# Power_Supply.net
KiCad netlist of a schematic drawn in Altium Designer
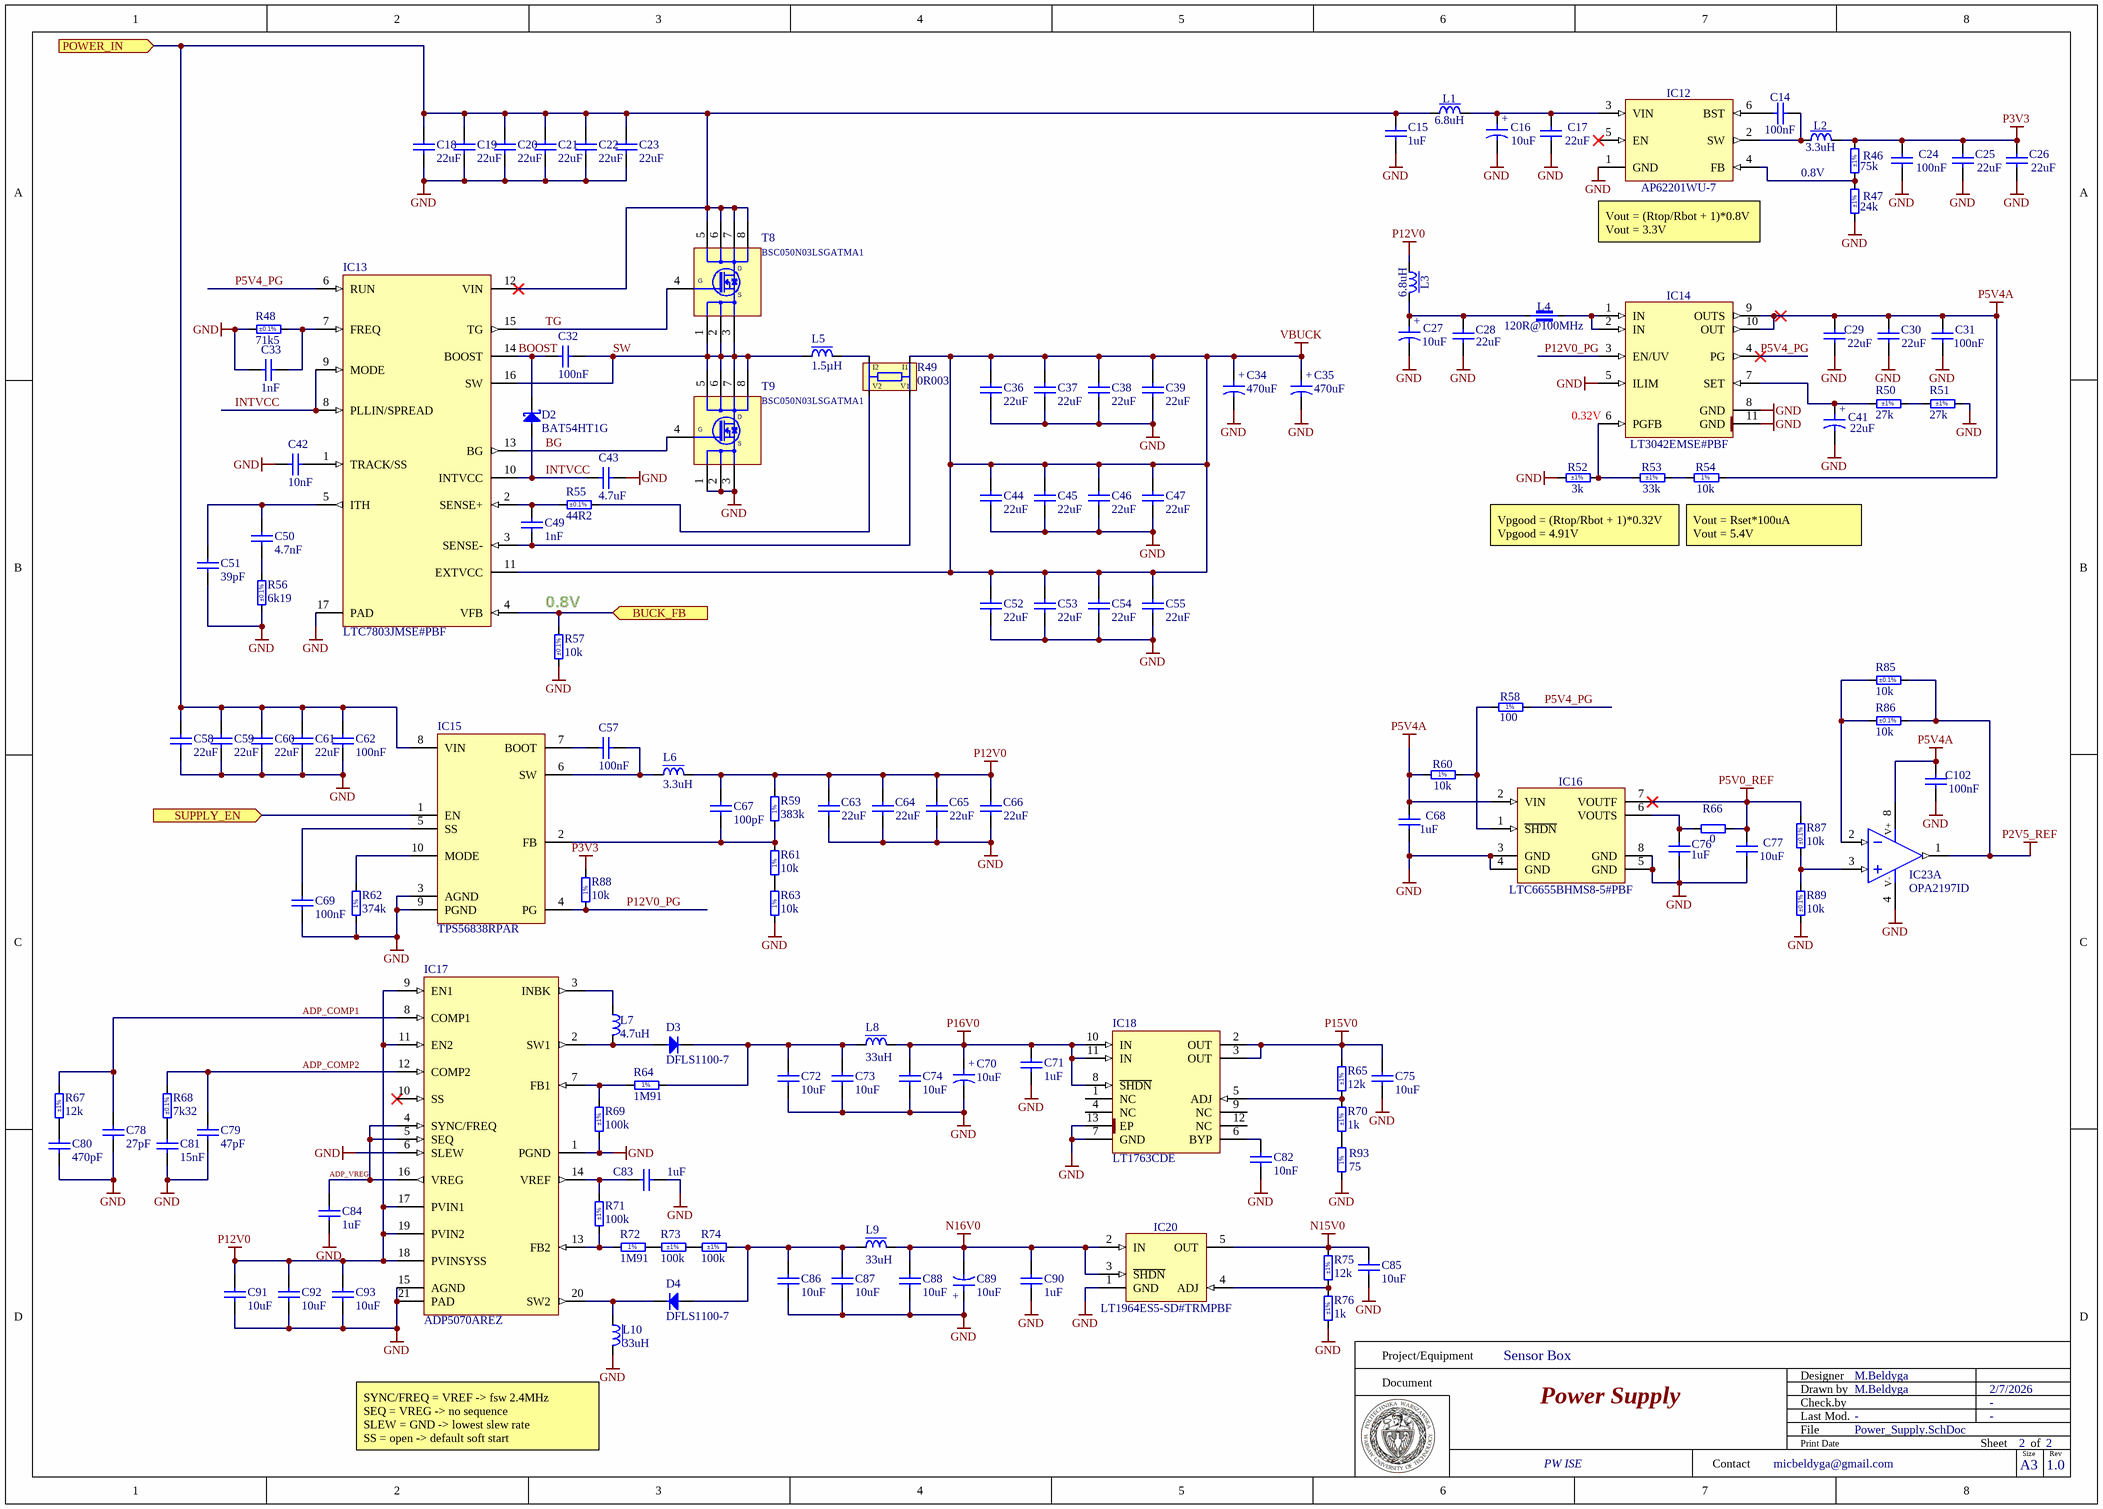
[diagram p0: Power_Supply.SchDoc]

(export (version "E")
  (design (tool "Eeschema 10.0.6"))
  (components
    (comp (ref "C14")
      (value "100nF")
      (footprint "CAPC1005X55N")
      (description "Non-polarised capacitor")
      (fields
        (field (name "PART NUMBER") "CC0402_100NF_16V_10%_X5R")
        (field (name "VOLTAGE") "16V")
        (field (name "AUTHOR") "CERN DEM JLC")
      )
      (libsource (lib "Capacitors") (part "Capacitor - non polarized"))
    )
    (comp (ref "C15")
      (value "1uF")
      (footprint "CAPC1608X87N")
      (description "Non-polarised capacitor")
      (fields
        (field (name "PART NUMBER") "CC0603_1UF_25V_10%_X7R")
        (field (name "VOLTAGE") "25V")
        (field (name "AUTHOR") "CERN DEM JLC")
      )
      (libsource (lib "Capacitors") (part "Capacitor - non polarized"))
    )
    (comp (ref "C16")
      (value "10uF")
      (footprint "CAPMP3216X180N")
      (description "Polarised capacitor")
      (fields
        (field (name "PART NUMBER") "CTE3216-18_10UF_16V_20%_AVX_TCJ")
        (field (name "VOLTAGE") "16V")
        (field (name "AUTHOR") "CERN DEM JLC")
      )
      (libsource (lib "Capacitors") (part "Capacitor - polarized"))
    )
    (comp (ref "C17")
      (value "22uF")
      (footprint "CAPC2012X135N")
      (description "Non-polarised capacitor")
      (fields
        (field (name "PART NUMBER") "CC0805_22UF_16V_10%_X5R")
        (field (name "VOLTAGE") "16V")
        (field (name "AUTHOR") "CERN DEM JLC")
      )
      (libsource (lib "Capacitors") (part "Capacitor - non polarized"))
    )
    (comp (ref "C18")
      (value "22uF")
      (footprint "CAPC3216X180N")
      (description "Non-polarised capacitor")
      (fields
        (field (name "PART NUMBER") "CC1206_22UF_35V_20%_X5R")
        (field (name "VOLTAGE") "35V")
        (field (name "AUTHOR") "CERN DEM BC")
      )
      (libsource (lib "Capacitors") (part "Capacitor - non polarized"))
    )
    (comp (ref "C19")
      (value "22uF")
      (footprint "CAPC3216X180N")
      (description "Non-polarised capacitor")
      (fields
        (field (name "PART NUMBER") "CC1206_22UF_35V_20%_X5R")
        (field (name "VOLTAGE") "35V")
        (field (name "AUTHOR") "CERN DEM BC")
      )
      (libsource (lib "Capacitors") (part "Capacitor - non polarized"))
    )
    (comp (ref "C20")
      (value "22uF")
      (footprint "CAPC3216X180N")
      (description "Non-polarised capacitor")
      (fields
        (field (name "PART NUMBER") "CC1206_22UF_35V_20%_X5R")
        (field (name "VOLTAGE") "35V")
        (field (name "AUTHOR") "CERN DEM BC")
      )
      (libsource (lib "Capacitors") (part "Capacitor - non polarized"))
    )
    (comp (ref "C21")
      (value "22uF")
      (footprint "CAPC3216X180N")
      (description "Non-polarised capacitor")
      (fields
        (field (name "PART NUMBER") "CC1206_22UF_35V_20%_X5R")
        (field (name "VOLTAGE") "35V")
        (field (name "AUTHOR") "CERN DEM BC")
      )
      (libsource (lib "Capacitors") (part "Capacitor - non polarized"))
    )
    (comp (ref "C22")
      (value "22uF")
      (footprint "CAPC3216X180N")
      (description "Non-polarised capacitor")
      (fields
        (field (name "PART NUMBER") "CC1206_22UF_35V_20%_X5R")
        (field (name "VOLTAGE") "35V")
        (field (name "AUTHOR") "CERN DEM BC")
      )
      (libsource (lib "Capacitors") (part "Capacitor - non polarized"))
    )
    (comp (ref "C23")
      (value "22uF")
      (footprint "CAPC3216X180N")
      (description "Non-polarised capacitor")
      (fields
        (field (name "PART NUMBER") "CC1206_22UF_35V_20%_X5R")
        (field (name "VOLTAGE") "35V")
        (field (name "AUTHOR") "CERN DEM BC")
      )
      (libsource (lib "Capacitors") (part "Capacitor - non polarized"))
    )
    (comp (ref "C24")
      (value "100nF")
      (footprint "CAPC1005X55N")
      (description "Non-polarised capacitor")
      (fields
        (field (name "PART NUMBER") "CC0402_100NF_16V_10%_X5R")
        (field (name "VOLTAGE") "16V")
        (field (name "AUTHOR") "CERN DEM JLC")
      )
      (libsource (lib "Capacitors") (part "Capacitor - non polarized"))
    )
    (comp (ref "C25")
      (value "22uF")
      (footprint "CAPC2012X135N")
      (description "Non-polarised capacitor")
      (fields
        (field (name "PART NUMBER") "CC0805_22UF_16V_10%_X5R")
        (field (name "VOLTAGE") "16V")
        (field (name "AUTHOR") "CERN DEM JLC")
      )
      (libsource (lib "Capacitors") (part "Capacitor - non polarized"))
    )
    (comp (ref "C26")
      (value "22uF")
      (footprint "CAPC2012X135N")
      (description "Non-polarised capacitor")
      (fields
        (field (name "PART NUMBER") "CC0805_22UF_16V_10%_X5R")
        (field (name "VOLTAGE") "16V")
        (field (name "AUTHOR") "CERN DEM JLC")
      )
      (libsource (lib "Capacitors") (part "Capacitor - non polarized"))
    )
    (comp (ref "C27")
      (value "10uF")
      (footprint "CAPMP3216X180N")
      (description "Polarised capacitor")
      (fields
        (field (name "PART NUMBER") "CTE3216-18_10UF_16V_20%_AVX_TCJ")
        (field (name "VOLTAGE") "16V")
        (field (name "AUTHOR") "CERN DEM JLC")
      )
      (libsource (lib "Capacitors") (part "Capacitor - polarized"))
    )
    (comp (ref "C28")
      (value "22uF")
      (footprint "CAPC2012X135N")
      (description "Non-polarised capacitor")
      (fields
        (field (name "PART NUMBER") "CC0805_22UF_16V_10%_X5R")
        (field (name "VOLTAGE") "16V")
        (field (name "AUTHOR") "CERN DEM JLC")
      )
      (libsource (lib "Capacitors") (part "Capacitor - non polarized"))
    )
    (comp (ref "C29")
      (value "22uF")
      (footprint "CAPC2012X135N")
      (description "Non-polarised capacitor")
      (fields
        (field (name "PART NUMBER") "CC0805_22UF_16V_10%_X5R")
        (field (name "VOLTAGE") "16V")
        (field (name "AUTHOR") "CERN DEM JLC")
      )
      (libsource (lib "Capacitors") (part "Capacitor - non polarized"))
    )
    (comp (ref "C30")
      (value "22uF")
      (footprint "CAPC2012X135N")
      (description "Non-polarised capacitor")
      (fields
        (field (name "PART NUMBER") "CC0805_22UF_16V_10%_X5R")
        (field (name "VOLTAGE") "16V")
        (field (name "AUTHOR") "CERN DEM JLC")
      )
      (libsource (lib "Capacitors") (part "Capacitor - non polarized"))
    )
    (comp (ref "C31")
      (value "100nF")
      (footprint "CAPC1005X55N")
      (description "Non-polarised capacitor")
      (fields
        (field (name "PART NUMBER") "CC0402_100NF_16V_10%_X5R")
        (field (name "VOLTAGE") "16V")
        (field (name "AUTHOR") "CERN DEM JLC")
      )
      (libsource (lib "Capacitors") (part "Capacitor - non polarized"))
    )
    (comp (ref "C32")
      (value "100nF")
      (footprint "CAPC1005X55N")
      (description "Non-polarised capacitor")
      (fields
        (field (name "PART NUMBER") "CC0402_100NF_50V_10%_X7R")
        (field (name "VOLTAGE") "50V")
        (field (name "AUTHOR") "CERN DEM MR")
      )
      (libsource (lib "Capacitors") (part "Capacitor - non polarized"))
    )
    (comp (ref "C33")
      (value "1nF")
      (footprint "CAPC1005X55N")
      (description "Non-polarised capacitor")
      (fields
        (field (name "PART NUMBER") "CC0402_1NF_50V_5%_C0G")
        (field (name "VOLTAGE") "50V")
        (field (name "AUTHOR") "CERN DEM BC")
      )
      (libsource (lib "Capacitors") (part "Capacitor - non polarized"))
    )
    (comp (ref "C34")
      (value "470uF")
      (footprint "CAPAE1030X1020N")
      (description "Polarised capacitor")
      (fields
        (field (name "PART NUMBER") "CAE1030-1020_470UF_25V_20%")
        (field (name "VOLTAGE") "25V")
        (field (name "AUTHOR") "CERN DEM JLC")
      )
      (libsource (lib "Capacitors") (part "Capacitor - polarized"))
    )
    (comp (ref "C35")
      (value "470uF")
      (footprint "CAPAE1030X1020N")
      (description "Polarised capacitor")
      (fields
        (field (name "PART NUMBER") "CAE1030-1020_470UF_25V_20%")
        (field (name "VOLTAGE") "25V")
        (field (name "AUTHOR") "CERN DEM JLC")
      )
      (libsource (lib "Capacitors") (part "Capacitor - polarized"))
    )
    (comp (ref "C36")
      (value "22uF")
      (footprint "CAPC3216X180N")
      (description "Non-polarised capacitor")
      (fields
        (field (name "PART NUMBER") "CC1206_22UF_25V_20%_X5R")
        (field (name "VOLTAGE") "25V")
        (field (name "AUTHOR") "CERN DEM WB")
      )
      (libsource (lib "Capacitors") (part "Capacitor - non polarized"))
    )
    (comp (ref "C37")
      (value "22uF")
      (footprint "CAPC3216X180N")
      (description "Non-polarised capacitor")
      (fields
        (field (name "PART NUMBER") "CC1206_22UF_25V_20%_X5R")
        (field (name "VOLTAGE") "25V")
        (field (name "AUTHOR") "CERN DEM WB")
      )
      (libsource (lib "Capacitors") (part "Capacitor - non polarized"))
    )
    (comp (ref "C38")
      (value "22uF")
      (footprint "CAPC3216X180N")
      (description "Non-polarised capacitor")
      (fields
        (field (name "PART NUMBER") "CC1206_22UF_25V_20%_X5R")
        (field (name "VOLTAGE") "25V")
        (field (name "AUTHOR") "CERN DEM WB")
      )
      (libsource (lib "Capacitors") (part "Capacitor - non polarized"))
    )
    (comp (ref "C39")
      (value "22uF")
      (footprint "CAPC3216X180N")
      (description "Non-polarised capacitor")
      (fields
        (field (name "PART NUMBER") "CC1206_22UF_25V_20%_X5R")
        (field (name "VOLTAGE") "25V")
        (field (name "AUTHOR") "CERN DEM WB")
      )
      (libsource (lib "Capacitors") (part "Capacitor - non polarized"))
    )
    (comp (ref "C41")
      (value "22uF")
      (footprint "CAPMP3528X210N")
      (description "Polarised capacitor")
      (fields
        (field (name "PART NUMBER") "CTE3528-21_22UF_10V_10%_LESR0700")
        (field (name "VOLTAGE") "10V")
        (field (name "AUTHOR") "CERN DEM JLC")
      )
      (libsource (lib "Capacitors") (part "Capacitor - polarized"))
    )
    (comp (ref "C42")
      (value "10nF")
      (footprint "CAPC1005X55N")
      (description "Non-polarised capacitor")
      (fields
        (field (name "PART NUMBER") "CC0402_10NF_25V_10%_X7R")
        (field (name "VOLTAGE") "25V")
        (field (name "AUTHOR") "CERN DEM JLC")
      )
      (libsource (lib "Capacitors") (part "Capacitor - non polarized"))
    )
    (comp (ref "C43")
      (value "4.7uF")
      (footprint "CAPC1005X55N")
      (description "Non-polarised capacitor")
      (fields
        (field (name "PART NUMBER") "CC0402_4.7UF_10V_10%_X5R")
        (field (name "VOLTAGE") "10V")
        (field (name "AUTHOR") "CERN DEM BC")
      )
      (libsource (lib "Capacitors") (part "Capacitor - non polarized"))
    )
    (comp (ref "C44")
      (value "22uF")
      (footprint "CAPC3216X180N")
      (description "Non-polarised capacitor")
      (fields
        (field (name "PART NUMBER") "CC1206_22UF_25V_20%_X5R")
        (field (name "VOLTAGE") "25V")
        (field (name "AUTHOR") "CERN DEM WB")
      )
      (libsource (lib "Capacitors") (part "Capacitor - non polarized"))
    )
    (comp (ref "C45")
      (value "22uF")
      (footprint "CAPC3216X180N")
      (description "Non-polarised capacitor")
      (fields
        (field (name "PART NUMBER") "CC1206_22UF_25V_20%_X5R")
        (field (name "VOLTAGE") "25V")
        (field (name "AUTHOR") "CERN DEM WB")
      )
      (libsource (lib "Capacitors") (part "Capacitor - non polarized"))
    )
    (comp (ref "C46")
      (value "22uF")
      (footprint "CAPC3216X180N")
      (description "Non-polarised capacitor")
      (fields
        (field (name "PART NUMBER") "CC1206_22UF_25V_20%_X5R")
        (field (name "VOLTAGE") "25V")
        (field (name "AUTHOR") "CERN DEM WB")
      )
      (libsource (lib "Capacitors") (part "Capacitor - non polarized"))
    )
    (comp (ref "C47")
      (value "22uF")
      (footprint "CAPC3216X180N")
      (description "Non-polarised capacitor")
      (fields
        (field (name "PART NUMBER") "CC1206_22UF_25V_20%_X5R")
        (field (name "VOLTAGE") "25V")
        (field (name "AUTHOR") "CERN DEM WB")
      )
      (libsource (lib "Capacitors") (part "Capacitor - non polarized"))
    )
    (comp (ref "C49")
      (value "1nF")
      (footprint "CAPC1005X55N")
      (description "Non-polarised capacitor")
      (fields
        (field (name "PART NUMBER") "CC0402_1NF_50V_5%_C0G")
        (field (name "VOLTAGE") "50V")
        (field (name "AUTHOR") "CERN DEM BC")
      )
      (libsource (lib "Capacitors") (part "Capacitor - non polarized"))
    )
    (comp (ref "C50")
      (value "4.7nF")
      (footprint "CAPC1005X55N")
      (description "Non-polarised capacitor")
      (fields
        (field (name "PART NUMBER") "CC0402_4.7NF_16V_10%_X7R")
        (field (name "VOLTAGE") "16V")
        (field (name "AUTHOR") "CERN DEM JLC")
      )
      (libsource (lib "Capacitors") (part "Capacitor - non polarized"))
    )
    (comp (ref "C51")
      (value "39pF")
      (footprint "CAPC1005X55N")
      (description "Non-polarised capacitor")
      (fields
        (field (name "PART NUMBER") "CC0402_39PF_100V_5%_C0G_MURATA_GRM1555C2A390JA01")
        (field (name "VOLTAGE") "100V")
        (field (name "AUTHOR") "CERN DEM BC")
      )
      (libsource (lib "Capacitors") (part "Capacitor - non polarized"))
    )
    (comp (ref "C52")
      (value "22uF")
      (footprint "CAPC3216X180N")
      (description "Non-polarised capacitor")
      (fields
        (field (name "PART NUMBER") "CC1206_22UF_25V_20%_X5R")
        (field (name "VOLTAGE") "25V")
        (field (name "AUTHOR") "CERN DEM WB")
      )
      (libsource (lib "Capacitors") (part "Capacitor - non polarized"))
    )
    (comp (ref "C53")
      (value "22uF")
      (footprint "CAPC3216X180N")
      (description "Non-polarised capacitor")
      (fields
        (field (name "PART NUMBER") "CC1206_22UF_25V_20%_X5R")
        (field (name "VOLTAGE") "25V")
        (field (name "AUTHOR") "CERN DEM WB")
      )
      (libsource (lib "Capacitors") (part "Capacitor - non polarized"))
    )
    (comp (ref "C54")
      (value "22uF")
      (footprint "CAPC3216X180N")
      (description "Non-polarised capacitor")
      (fields
        (field (name "PART NUMBER") "CC1206_22UF_25V_20%_X5R")
        (field (name "VOLTAGE") "25V")
        (field (name "AUTHOR") "CERN DEM WB")
      )
      (libsource (lib "Capacitors") (part "Capacitor - non polarized"))
    )
    (comp (ref "C55")
      (value "22uF")
      (footprint "CAPC3216X180N")
      (description "Non-polarised capacitor")
      (fields
        (field (name "PART NUMBER") "CC1206_22UF_25V_20%_X5R")
        (field (name "VOLTAGE") "25V")
        (field (name "AUTHOR") "CERN DEM WB")
      )
      (libsource (lib "Capacitors") (part "Capacitor - non polarized"))
    )
    (comp (ref "C57")
      (value "100nF")
      (footprint "CAPC1005X55N")
      (description "Non-polarised capacitor")
      (fields
        (field (name "PART NUMBER") "CC0402_100NF_16V_10%_X5R")
        (field (name "VOLTAGE") "16V")
        (field (name "AUTHOR") "CERN DEM JLC")
      )
      (libsource (lib "Capacitors") (part "Capacitor - non polarized"))
    )
    (comp (ref "C58")
      (value "22uF")
      (footprint "CAPC3216X180N")
      (description "Non-polarised capacitor")
      (fields
        (field (name "PART NUMBER") "CC1206_22UF_35V_20%_X5R")
        (field (name "VOLTAGE") "35V")
        (field (name "AUTHOR") "CERN DEM BC")
      )
      (libsource (lib "Capacitors") (part "Capacitor - non polarized"))
    )
    (comp (ref "C59")
      (value "22uF")
      (footprint "CAPC3216X180N")
      (description "Non-polarised capacitor")
      (fields
        (field (name "PART NUMBER") "CC1206_22UF_35V_20%_X5R")
        (field (name "VOLTAGE") "35V")
        (field (name "AUTHOR") "CERN DEM BC")
      )
      (libsource (lib "Capacitors") (part "Capacitor - non polarized"))
    )
    (comp (ref "C60")
      (value "22uF")
      (footprint "CAPC3216X180N")
      (description "Non-polarised capacitor")
      (fields
        (field (name "PART NUMBER") "CC1206_22UF_35V_20%_X5R")
        (field (name "VOLTAGE") "35V")
        (field (name "AUTHOR") "CERN DEM BC")
      )
      (libsource (lib "Capacitors") (part "Capacitor - non polarized"))
    )
    (comp (ref "C61")
      (value "22uF")
      (footprint "CAPC3216X180N")
      (description "Non-polarised capacitor")
      (fields
        (field (name "PART NUMBER") "CC1206_22UF_35V_20%_X5R")
        (field (name "VOLTAGE") "35V")
        (field (name "AUTHOR") "CERN DEM BC")
      )
      (libsource (lib "Capacitors") (part "Capacitor - non polarized"))
    )
    (comp (ref "C62")
      (value "100nF")
      (footprint "CAPC1005X55N")
      (description "Non-polarised capacitor")
      (fields
        (field (name "PART NUMBER") "CC0402_100NF_16V_10%_X5R")
        (field (name "VOLTAGE") "16V")
        (field (name "AUTHOR") "CERN DEM JLC")
      )
      (libsource (lib "Capacitors") (part "Capacitor - non polarized"))
    )
    (comp (ref "C63")
      (value "22uF")
      (footprint "CAPC2012X135N")
      (description "Non-polarised capacitor")
      (fields
        (field (name "PART NUMBER") "CC0805_22UF_16V_10%_X5R")
        (field (name "VOLTAGE") "16V")
        (field (name "AUTHOR") "CERN DEM JLC")
      )
      (libsource (lib "Capacitors") (part "Capacitor - non polarized"))
    )
    (comp (ref "C64")
      (value "22uF")
      (footprint "CAPC2012X135N")
      (description "Non-polarised capacitor")
      (fields
        (field (name "PART NUMBER") "CC0805_22UF_16V_10%_X5R")
        (field (name "VOLTAGE") "16V")
        (field (name "AUTHOR") "CERN DEM JLC")
      )
      (libsource (lib "Capacitors") (part "Capacitor - non polarized"))
    )
    (comp (ref "C65")
      (value "22uF")
      (footprint "CAPC2012X135N")
      (description "Non-polarised capacitor")
      (fields
        (field (name "PART NUMBER") "CC0805_22UF_16V_10%_X5R")
        (field (name "VOLTAGE") "16V")
        (field (name "AUTHOR") "CERN DEM JLC")
      )
      (libsource (lib "Capacitors") (part "Capacitor - non polarized"))
    )
    (comp (ref "C66")
      (value "22uF")
      (footprint "CAPC2012X135N")
      (description "Non-polarised capacitor")
      (fields
        (field (name "PART NUMBER") "CC0805_22UF_16V_10%_X5R")
        (field (name "VOLTAGE") "16V")
        (field (name "AUTHOR") "CERN DEM JLC")
      )
      (libsource (lib "Capacitors") (part "Capacitor - non polarized"))
    )
    (comp (ref "C67")
      (value "100pF")
      (footprint "CAPC1005X55N")
      (description "SMD Mulitlayer Ceramic Chip Capacitor")
      (fields
        (field (name "PART NUMBER") "CC0402_100PF_50V_5%_C0G")
        (field (name "VOLTAGE") "50V")
        (field (name "AUTHOR") "Michal Beldyga")
      )
      (libsource (lib "Capacitors") (part "Capacitor - non polarized"))
    )
    (comp (ref "C68")
      (value "1uF")
      (footprint "CAPC1608X87N")
      (description "Non-polarised capacitor")
      (fields
        (field (name "PART NUMBER") "CC0603_1UF_25V_10%_X7R")
        (field (name "VOLTAGE") "25V")
        (field (name "AUTHOR") "CERN DEM JLC")
      )
      (libsource (lib "Capacitors") (part "Capacitor - non polarized"))
    )
    (comp (ref "C69")
      (value "100nF")
      (footprint "CAPC1005X55N")
      (description "Non-polarised capacitor")
      (fields
        (field (name "PART NUMBER") "CC0402_100NF_16V_10%_X5R")
        (field (name "VOLTAGE") "16V")
        (field (name "AUTHOR") "CERN DEM JLC")
      )
      (libsource (lib "Capacitors") (part "Capacitor - non polarized"))
    )
    (comp (ref "C70")
      (value "10uF")
      (footprint "CAPMP3216X180N")
      (description "Polarised capacitor")
      (fields
        (field (name "PART NUMBER") "CTE3216-18_10UF_16V_20%_AVX_TCJ")
        (field (name "VOLTAGE") "16V")
        (field (name "AUTHOR") "CERN DEM JLC")
      )
      (libsource (lib "Capacitors") (part "Capacitor - polarized"))
    )
    (comp (ref "C71")
      (value "1uF")
      (footprint "CAPC1608X87N")
      (description "Non-polarised capacitor")
      (fields
        (field (name "PART NUMBER") "CC0603_1UF_25V_10%_X7R")
        (field (name "VOLTAGE") "25V")
        (field (name "AUTHOR") "CERN DEM JLC")
      )
      (libsource (lib "Capacitors") (part "Capacitor - non polarized"))
    )
    (comp (ref "C72")
      (value "10uF")
      (footprint "CAPC1709X100N")
      (description "Non-polarised capacitor")
      (fields
        (field (name "PART NUMBER") "CC0603_10UF_25V_20%_X5R")
        (field (name "VOLTAGE") "25V")
        (field (name "AUTHOR") "CERN DEM BC")
      )
      (libsource (lib "Capacitors") (part "Capacitor - non polarized"))
    )
    (comp (ref "C73")
      (value "10uF")
      (footprint "CAPC1709X100N")
      (description "Non-polarised capacitor")
      (fields
        (field (name "PART NUMBER") "CC0603_10UF_25V_20%_X5R")
        (field (name "VOLTAGE") "25V")
        (field (name "AUTHOR") "CERN DEM BC")
      )
      (libsource (lib "Capacitors") (part "Capacitor - non polarized"))
    )
    (comp (ref "C74")
      (value "10uF")
      (footprint "CAPC1709X100N")
      (description "Non-polarised capacitor")
      (fields
        (field (name "PART NUMBER") "CC0603_10UF_25V_20%_X5R")
        (field (name "VOLTAGE") "25V")
        (field (name "AUTHOR") "CERN DEM BC")
      )
      (libsource (lib "Capacitors") (part "Capacitor - non polarized"))
    )
    (comp (ref "C75")
      (value "10uF")
      (footprint "CAPC1709X100N")
      (description "Non-polarised capacitor")
      (fields
        (field (name "PART NUMBER") "CC0603_10UF_25V_20%_X5R")
        (field (name "VOLTAGE") "25V")
        (field (name "AUTHOR") "CERN DEM BC")
      )
      (libsource (lib "Capacitors") (part "Capacitor - non polarized"))
    )
    (comp (ref "C76")
      (value "1uF")
      (footprint "CAPC1608X87N")
      (description "Non-polarised capacitor")
      (fields
        (field (name "PART NUMBER") "CC0603_1UF_25V_10%_X7R")
        (field (name "VOLTAGE") "25V")
        (field (name "AUTHOR") "CERN DEM JLC")
      )
      (libsource (lib "Capacitors") (part "Capacitor - non polarized"))
    )
    (comp (ref "C77")
      (value "10uF")
      (footprint "CAPC1608X80N")
      (description "Non-polarised capacitor")
      (fields
        (field (name "PART NUMBER") "CC0603_10UF_16V_20%_X5R")
        (field (name "VOLTAGE") "16V")
        (field (name "AUTHOR") "CERN DEM MR")
      )
      (libsource (lib "Capacitors") (part "Capacitor - non polarized"))
    )
    (comp (ref "C78")
      (value "27pF")
      (footprint "CAPC1005X55N")
      (description "Non-polarised capacitor")
      (fields
        (field (name "PART NUMBER") "CC0402_27PF_50V_5%_C0G")
        (field (name "VOLTAGE") "50V")
        (field (name "AUTHOR") "CERN DEM JLC")
      )
      (libsource (lib "Capacitors") (part "Capacitor - non polarized"))
    )
    (comp (ref "C79")
      (value "47pF")
      (footprint "CAPC1005X55N")
      (description "Non-polarised capacitor")
      (fields
        (field (name "PART NUMBER") "CC0402_47PF_50V_5%_C0G")
        (field (name "VOLTAGE") "50V")
        (field (name "AUTHOR") "CERN DEM JLC")
      )
      (libsource (lib "Capacitors") (part "Capacitor - non polarized"))
    )
    (comp (ref "C80")
      (value "470pF")
      (footprint "CAPC1005X55N")
      (description "Non-polarised capacitor")
      (fields
        (field (name "PART NUMBER") "CC0402_470PF_50V_10%_X7R")
        (field (name "VOLTAGE") "50V")
        (field (name "AUTHOR") "CERN DEM JLC")
      )
      (libsource (lib "Capacitors") (part "Capacitor - non polarized"))
    )
    (comp (ref "C81")
      (value "15nF")
      (footprint "CAPC1005X55N")
      (description "Non-polarised capacitor")
      (fields
        (field (name "PART NUMBER") "CC0402_15NF_50V_5%_X7R")
        (field (name "VOLTAGE") "50V")
        (field (name "AUTHOR") "CERN DEM BC")
      )
      (libsource (lib "Capacitors") (part "Capacitor - non polarized"))
    )
    (comp (ref "C82")
      (value "10nF")
      (footprint "CAPC1005X55N")
      (description "Non-polarised capacitor")
      (fields
        (field (name "PART NUMBER") "CC0402_10NF_50V_5%_X7R")
        (field (name "VOLTAGE") "50V")
        (field (name "AUTHOR") "CERN DEM BC")
      )
      (libsource (lib "Capacitors") (part "Capacitor - non polarized"))
    )
    (comp (ref "C83")
      (value "1uF")
      (footprint "CAPC1608X87N")
      (description "Non-polarised capacitor")
      (fields
        (field (name "PART NUMBER") "CC0603_1UF_25V_10%_X7R")
        (field (name "VOLTAGE") "25V")
        (field (name "AUTHOR") "CERN DEM JLC")
      )
      (libsource (lib "Capacitors") (part "Capacitor - non polarized"))
    )
    (comp (ref "C84")
      (value "1uF")
      (footprint "CAPC1608X87N")
      (description "Non-polarised capacitor")
      (fields
        (field (name "PART NUMBER") "CC0603_1UF_25V_10%_X7R")
        (field (name "VOLTAGE") "25V")
        (field (name "AUTHOR") "CERN DEM JLC")
      )
      (libsource (lib "Capacitors") (part "Capacitor - non polarized"))
    )
    (comp (ref "C85")
      (value "10uF")
      (footprint "CAPC1709X100N")
      (description "Non-polarised capacitor")
      (fields
        (field (name "PART NUMBER") "CC0603_10UF_25V_20%_X5R")
        (field (name "VOLTAGE") "25V")
        (field (name "AUTHOR") "CERN DEM BC")
      )
      (libsource (lib "Capacitors") (part "Capacitor - non polarized"))
    )
    (comp (ref "C86")
      (value "10uF")
      (footprint "CAPC1709X100N")
      (description "Non-polarised capacitor")
      (fields
        (field (name "PART NUMBER") "CC0603_10UF_25V_20%_X5R")
        (field (name "VOLTAGE") "25V")
        (field (name "AUTHOR") "CERN DEM BC")
      )
      (libsource (lib "Capacitors") (part "Capacitor - non polarized"))
    )
    (comp (ref "C87")
      (value "10uF")
      (footprint "CAPC1709X100N")
      (description "Non-polarised capacitor")
      (fields
        (field (name "PART NUMBER") "CC0603_10UF_25V_20%_X5R")
        (field (name "VOLTAGE") "25V")
        (field (name "AUTHOR") "CERN DEM BC")
      )
      (libsource (lib "Capacitors") (part "Capacitor - non polarized"))
    )
    (comp (ref "C88")
      (value "10uF")
      (footprint "CAPC1709X100N")
      (description "Non-polarised capacitor")
      (fields
        (field (name "PART NUMBER") "CC0603_10UF_25V_20%_X5R")
        (field (name "VOLTAGE") "25V")
        (field (name "AUTHOR") "CERN DEM BC")
      )
      (libsource (lib "Capacitors") (part "Capacitor - non polarized"))
    )
    (comp (ref "C89")
      (value "10uF")
      (footprint "CAPMP3216X180N")
      (description "Polarised capacitor")
      (fields
        (field (name "PART NUMBER") "CTE3216-18_10UF_16V_20%_AVX_TCJ")
        (field (name "VOLTAGE") "16V")
        (field (name "AUTHOR") "CERN DEM JLC")
      )
      (libsource (lib "Capacitors") (part "Capacitor - polarized"))
    )
    (comp (ref "C90")
      (value "1uF")
      (footprint "CAPC1608X87N")
      (description "Non-polarised capacitor")
      (fields
        (field (name "PART NUMBER") "CC0603_1UF_25V_10%_X7R")
        (field (name "VOLTAGE") "25V")
        (field (name "AUTHOR") "CERN DEM JLC")
      )
      (libsource (lib "Capacitors") (part "Capacitor - non polarized"))
    )
    (comp (ref "C91")
      (value "10uF")
      (footprint "CAPC1709X100N")
      (description "Non-polarised capacitor")
      (fields
        (field (name "PART NUMBER") "CC0603_10UF_25V_20%_X5R")
        (field (name "VOLTAGE") "25V")
        (field (name "AUTHOR") "CERN DEM BC")
      )
      (libsource (lib "Capacitors") (part "Capacitor - non polarized"))
    )
    (comp (ref "C92")
      (value "10uF")
      (footprint "CAPC1709X100N")
      (description "Non-polarised capacitor")
      (fields
        (field (name "PART NUMBER") "CC0603_10UF_25V_20%_X5R")
        (field (name "VOLTAGE") "25V")
        (field (name "AUTHOR") "CERN DEM BC")
      )
      (libsource (lib "Capacitors") (part "Capacitor - non polarized"))
    )
    (comp (ref "C93")
      (value "10uF")
      (footprint "CAPC1709X100N")
      (description "Non-polarised capacitor")
      (fields
        (field (name "PART NUMBER") "CC0603_10UF_25V_20%_X5R")
        (field (name "VOLTAGE") "25V")
        (field (name "AUTHOR") "CERN DEM BC")
      )
      (libsource (lib "Capacitors") (part "Capacitor - non polarized"))
    )
    (comp (ref "C102")
      (value "100nF")
      (footprint "CAPC1005X55N")
      (description "Non-polarised capacitor")
      (fields
        (field (name "PART NUMBER") "CC0402_100NF_16V_10%_X5R")
        (field (name "VOLTAGE") "16V")
        (field (name "AUTHOR") "CERN DEM JLC")
      )
      (libsource (lib "Capacitors") (part "Capacitor - non polarized"))
    )
    (comp (ref "D2")
      (value "BAT54HT1G")
      (footprint "SOD2513X100N")
      (description "Schottky Diode")
      (fields
        (field (name "VOLTAGE") "30V")
        (field (name "POWER") "200mA")
        (field (name "AUTHOR") "CERN DEM BC")
      )
      (libsource (lib "ICs And Semiconductors") (part "Diode Schottky"))
    )
    (comp (ref "D3")
      (value "DFLS1100-7")
      (footprint "DIODES-INC_POWERDI123")
      (description "Diode")
      (fields
        (field (name "VOLTAGE") "100V")
        (field (name "POWER") "1A")
        (field (name "AUTHOR") "CERN DEM HF")
      )
      (libsource (lib "ICs And Semiconductors") (part "Diode"))
    )
    (comp (ref "D4")
      (value "DFLS1100-7")
      (footprint "DIODES-INC_POWERDI123")
      (description "Diode")
      (fields
        (field (name "VOLTAGE") "100V")
        (field (name "POWER") "1A")
        (field (name "AUTHOR") "CERN DEM HF")
      )
      (libsource (lib "ICs And Semiconductors") (part "Diode"))
    )
    (comp (ref "IC12")
      (value "AP62201WU-7")
      (footprint "SOT95P280X100-6N")
      (description "4.2V TO 18V INPUT, 2A LOW IQ SYNCHRONOUS BUCK CONVERTER")
      (fields (field (name "AUTHOR") "CERN DEM HF"))
      (libsource (lib "ICs And Semiconductors") (part "AP62201WU"))
    )
    (comp (ref "IC13")
      (value "LTC7803JMSE#PBF")
      (footprint "TSSOP50P490X86_HS-17N")
      (description "Switching Controller, Current-mode, 3000kHz Switching Freq-Max, CMOS, PDSO16")
      (fields (field (name "MANUFACTURER") "Analog Devices"))
      (libsource (lib "mb") (part "LTC7803JMSE#PBF"))
    )
    (comp (ref "IC14")
      (value "LT3042EMSE#PBF")
      (footprint "SOP50P490X110-11N-R168X198")
      (description "20V, 200mA, Ultralow Noise, Ultrahigh PSRR RF Linear Regulator")
      (fields (field (name "AUTHOR") "CERN DEM MR"))
      (libsource (lib "ICs And Semiconductors") (part "LT3042"))
    )
    (comp (ref "IC15")
      (value "TPS56838RPAR")
      (footprint "RPA0010A")
      (description "TPS5683x 4.5V to 28V Input, 8A Synchronous Buck Converter")
      (fields
        (field (name "MANUFACTURER") "Texas Instruments")
        (field (name "ARENA PART NUMBER") "150-000054")
        (field (name "AUTHOR") "Michal Beldyga")
      )
      (libsource (lib "Semiconductors") (part "TPS5683x"))
    )
    (comp (ref "IC16")
      (value "LTC6655BHMS8-5#PBF")
      (footprint "SOP65P490X110-8N")
      (description "0.25ppm Noise, Low Drift Precision Buffered Voltage Reference")
      (fields (field (name "AUTHOR") "CERN DEM JLC"))
      (libsource (lib "ICs And Semiconductors") (part "LTC6655"))
    )
    (comp (ref "IC17")
      (value "ADP5070AREZ")
      (footprint "SOP65P640X120-21N-R305X425")
      (description "1A/0.6A, DC-to-DC Switching Regulator with Independent Positive and Negative Outputs")
      (fields
        (field (name "MANUFACTURER") "ANALOG DEVICES")
        (field (name "MANUFACTURER PART NUMBER") "ADP5070ARE")
        (field (name "AUTHOR") "CERN DEM JLC")
      )
      (libsource (lib "mb") (part "ADP5070AREZ"))
    )
    (comp (ref "IC18")
      (value "LT1763CDE")
      (footprint "SON50P300X400X80-13N-R180X340")
      (description "1.22V to 20V 500mA, Low Noise, LDO Adjustable Micropower Regulator")
      (fields (field (name "MANUFACTURER") "LINEAR TECHNOLOGY") (field (name "AUTHOR") "CERN DEM HF"))
      (libsource (lib "ICs And Semiconductors") (part "LT1763xDE_a"))
    )
    (comp (ref "IC20")
      (value "LT1964ES5-SD#TRMPBF")
      (footprint "SOT95P280X100-5N")
      (description "200mA, Low Noise, Low Dropout Negative Micropower Regulator")
      (fields (field (name "MANUFACTURER") "LINEAR TECHNOLOGY") (field (name "AUTHOR") "CERN DEM JLC"))
      (libsource (lib "ICs And Semiconductors") (part "LT1964-SD"))
    )
    (comp (ref "IC23")
      (value "OPA2197ID")
      (footprint "SOIC127P600X175-8N")
      (description "Dual Operational Amplifier")
      (fields (field (name "MANUFACTURER") "TEXAS INSTRUMENTS") (field (name "AUTHOR") "CERN DEM MR"))
      (libsource (lib "ICs And Semiconductors") (part "Operational Amplifier x2 Type1"))
    )
    (comp (ref "L1")
      (value "6.8uH")
      (footprint "IND_COILCRAFT_XAL4030")
      (description "Inductor With Core")
      (fields
        (field (name "PART NUMBER") "IND_6.8UH_20%_COILCRAFT_XAL4030")
        (field (name "POWER") "3A")
        (field (name "AUTHOR") "CERN DEM MR")
      )
      (libsource (lib "Inductors & Transformers") (part "Inductor With Magnetic core"))
    )
    (comp (ref "L2")
      (value "3.3uH")
      (footprint "IND_WURTH_WE-TPC_4828")
      (description "Inductor With Core")
      (fields
        (field (name "PART NUMBER") "IND_3.3UH_30%_WURTH_WE-TPC_744043003")
        (field (name "POWER") "2.15A")
        (field (name "AUTHOR") "CERN DEM JLC")
      )
      (libsource (lib "Inductors & Transformers") (part "Inductor With Magnetic core"))
    )
    (comp (ref "L3")
      (value "6.8uH")
      (footprint "IND_COILCRAFT_XAL4030")
      (description "Inductor With Core")
      (fields
        (field (name "PART NUMBER") "IND_6.8UH_20%_COILCRAFT_XAL4030")
        (field (name "POWER") "3A")
        (field (name "AUTHOR") "CERN DEM MR")
      )
      (libsource (lib "") (part "Inductor With Magnetic core_1"))
    )
    (comp (ref "L4")
      (value "120R@100MHz")
      (footprint "INDC1608X65N")
      (fields
        (field (name "PART NUMBER") "IND0603_MURATA_BLM18SG121TN1D")
        (field (name "POWER") "3A")
        (field (name "TOLERANCE") "±25%")
        (field (name "AUTHOR") "CERN DEM JLC")
      )
      (libsource (lib "Inductors & Transformers") (part "Ferrite Bead"))
    )
    (comp (ref "L5")
      (value "1.5µH")
      (footprint "SPM10065VT-1R5M-D")
      (description "General Purpose Inductor, 1.5uH, 20%, 1 Element, Metal Composite-Core, SMD, 4139")
      (fields
        (field (name "MANUFACTURER") "TDK")
        (field (name "MANUFACTURER PART NUMBER") "SPM10065VT-1R5M-D")
      )
      (libsource (lib "mb") (part "SPM10065VT-1R5M-D"))
    )
    (comp (ref "L6")
      (value "3.3uH")
      (footprint "IND_WURTH_WE-PD_7332(METAL)")
      (description "Inductor With Core")
      (fields
        (field (name "PART NUMBER") "IND_3.3UH_20%_WURTH_WE-PD_744778003")
        (field (name "POWER") "3.1A")
        (field (name "AUTHOR") "CERN DEM JLC")
      )
      (libsource (lib "Inductors & Transformers") (part "Inductor With Magnetic core"))
    )
    (comp (ref "L7")
      (value "4.7uH")
      (footprint "IND_COILCRAFT_EPL3015")
      (description "Inductor")
      (fields
        (field (name "PART NUMBER") "IND_4.7UH_20%_COILCRAFT_EPL3015")
        (field (name "POWER") "1A")
        (field (name "AUTHOR") "CERN DEM BC")
      )
      (libsource (lib "Inductors & Transformers") (part "Inductor"))
    )
    (comp (ref "L8")
      (value "33uH")
      (footprint "IND_WURTH_WE-TPC_4828")
      (description "Inductor With Core")
      (fields
        (field (name "PART NUMBER") "IND_33UH_30%_WURTH_WE-TPC_744043330")
        (field (name "POWER") "820mA")
        (field (name "AUTHOR") "CERN DEM JLC")
      )
      (libsource (lib "Inductors & Transformers") (part "Inductor With Magnetic core"))
    )
    (comp (ref "L9")
      (value "33uH")
      (footprint "IND_WURTH_WE-TPC_4828")
      (description "Inductor With Core")
      (fields
        (field (name "PART NUMBER") "IND_33UH_30%_WURTH_WE-TPC_744043330")
        (field (name "POWER") "820mA")
        (field (name "AUTHOR") "CERN DEM JLC")
      )
      (libsource (lib "Inductors & Transformers") (part "Inductor With Magnetic core"))
    )
    (comp (ref "L10")
      (value "33uH")
      (footprint "IND_WURTH_WE-TPC_4828")
      (description "Inductor With Core")
      (fields
        (field (name "PART NUMBER") "IND_33UH_30%_WURTH_WE-TPC_744043330")
        (field (name "POWER") "820mA")
        (field (name "AUTHOR") "CERN DEM JLC")
      )
      (libsource (lib "") (part "Inductor With Magnetic core_1"))
    )
    (comp (ref "R46")
      (value "75k")
      (footprint "RESC1608X55N")
      (description "Resistor - 1%")
      (fields
        (field (name "TOLERANCE") "±1%")
        (field (name "PART NUMBER") "R0603_75K_1%_0.1W_100PPM")
        (field (name "POWER") "0.1W")
        (field (name "AUTHOR") "CERN DEM JLC")
      )
      (libsource (lib "Resistors") (part "Resistor - 1%"))
    )
    (comp (ref "R47")
      (value "24k")
      (footprint "RESC1608X55N")
      (description "Resistor - 1%")
      (fields
        (field (name "TOLERANCE") "±1%")
        (field (name "PART NUMBER") "R0603_24K_1%_0.1W_100PPM")
        (field (name "POWER") "0.1W")
        (field (name "AUTHOR") "CERN DEM JLC")
      )
      (libsource (lib "Resistors") (part "Resistor - 1%"))
    )
    (comp (ref "R48")
      (value "71k5")
      (footprint "RESC1608X55N")
      (description "Resistor - 0.1%")
      (fields
        (field (name "TOLERANCE") "±0.1%")
        (field (name "PART NUMBER") "R0603_71K5_0.1%_0.063W_10PPM")
        (field (name "POWER") "0.063W")
        (field (name "AUTHOR") "CERN DEM JLC")
      )
      (libsource (lib "Resistors") (part "Resistor - 0.1%"))
    )
    (comp (ref "R49")
      (value "0R003")
      (footprint "RES_OHMITE_LVK25")
      (description "Power and Current Sensing Resistor")
      (fields
        (field (name "PART NUMBER") "R_0R003_1%_2W_200PPM_OHMITE_LVK25")
        (field (name "POWER") "2W")
        (field (name "AUTHOR") "CERN DEM HF")
      )
      (libsource (lib "Resistors") (part "Current + Voltage Sense Resistor"))
    )
    (comp (ref "R50")
      (value "27k")
      (footprint "RESC1005X40N")
      (description "Resistor - 1%")
      (fields
        (field (name "TOLERANCE") "±1%")
        (field (name "PART NUMBER") "R0402_27K_1%_0.0625W_100PPM")
        (field (name "POWER") "0.0625W")
        (field (name "AUTHOR") "CERN DEM JLC")
      )
      (libsource (lib "Resistors") (part "Resistor - 1%"))
    )
    (comp (ref "R51")
      (value "27k")
      (footprint "RESC1005X40N")
      (description "Resistor - 1%")
      (fields
        (field (name "TOLERANCE") "±1%")
        (field (name "PART NUMBER") "R0402_27K_1%_0.0625W_100PPM")
        (field (name "POWER") "0.0625W")
        (field (name "AUTHOR") "CERN DEM JLC")
      )
      (libsource (lib "Resistors") (part "Resistor - 1%"))
    )
    (comp (ref "R52")
      (value "3k")
      (footprint "RESC1005X40N")
      (description "Resistor - 1%")
      (fields
        (field (name "TOLERANCE") "±1%")
        (field (name "PART NUMBER") "R0402_3K_1%_0.0625W_100PPM")
        (field (name "POWER") "0.0625W")
        (field (name "AUTHOR") "CERN DEM JLC")
      )
      (libsource (lib "Resistors") (part "Resistor - 1%"))
    )
    (comp (ref "R53")
      (value "33k")
      (footprint "RESC1608X55N")
      (description "Resistor - 1%")
      (fields
        (field (name "TOLERANCE") "±1%")
        (field (name "PART NUMBER") "R0603_33K_1%_0.1W_100PPM")
        (field (name "POWER") "0.1W")
        (field (name "AUTHOR") "CERN DEM JLC")
      )
      (libsource (lib "Resistors") (part "Resistor - 1%"))
    )
    (comp (ref "R54")
      (value "10k")
      (footprint "RESC1005X40N")
      (description "Resistor - 1%")
      (fields
        (field (name "PART NUMBER") "R0402_10K_1%_0.0625W_100PPM")
        (field (name "POWER") "0.0625W")
        (field (name "AUTHOR") "CERN DEM JLC")
      )
      (libsource (lib "Resistors") (part "Resistor - 1%"))
    )
    (comp (ref "R55")
      (value "44R2")
      (footprint "RESC1608X55N")
      (description "Resistor - 0.1%")
      (fields
        (field (name "TOLERANCE") "±0.1%")
        (field (name "PART NUMBER") "R0603_44R2_0.1%_0.063W_10PPM")
        (field (name "POWER") "0.063W")
        (field (name "AUTHOR") "CERN DEM JLC")
      )
      (libsource (lib "Resistors") (part "Resistor - 0.1%"))
    )
    (comp (ref "R56")
      (value "6k19")
      (footprint "RESC1608X55N")
      (description "Resistor - 0.1%")
      (fields
        (field (name "TOLERANCE") "±0.1%")
        (field (name "PART NUMBER") "R0603_6K19_0.1%_0.063W_10PPM")
        (field (name "POWER") "0.063W")
        (field (name "AUTHOR") "CERN DEM JLC")
      )
      (libsource (lib "Resistors") (part "Resistor - 0.1%"))
    )
    (comp (ref "R57")
      (value "10k")
      (footprint "RESC1005X35N")
      (description "Resistor - 0.1%")
      (fields
        (field (name "TOLERANCE") "±0.1%")
        (field (name "PART NUMBER") "R0402_10K_0.1%_0.063W_25PPM")
        (field (name "POWER") "0.063W")
        (field (name "AUTHOR") "CERN DEM JMW")
      )
      (libsource (lib "Resistors") (part "Resistor - 0.1%"))
    )
    (comp (ref "R58")
      (value "100")
      (footprint "RESC1005X40N")
      (description "Resistor - 1%")
      (fields
        (field (name "PART NUMBER") "R0402_100R_1%_0.0625W_100PPM")
        (field (name "POWER") "0.0625W")
        (field (name "AUTHOR") "CERN DEM JLC")
      )
      (libsource (lib "Resistors") (part "Resistor - 1%"))
    )
    (comp (ref "R59")
      (value "383k")
      (footprint "RESC1005X40N")
      (description "RES 383k OHM 1% 1/16W 0402")
      (fields
        (field (name "PART NUMBER") "R0402_383K_1%_0.0625W")
        (field (name "POWER") "0.0625W")
        (field (name "AUTHOR") "Michal Beldyga")
      )
      (libsource (lib "") (part "Resistor - 1%_1"))
    )
    (comp (ref "R60")
      (value "10k")
      (footprint "RESC1005X40N")
      (description "Resistor - 1%")
      (fields
        (field (name "PART NUMBER") "R0402_10K_1%_0.0625W_100PPM")
        (field (name "POWER") "0.0625W")
        (field (name "AUTHOR") "CERN DEM JLC")
      )
      (libsource (lib "Resistors") (part "Resistor - 1%"))
    )
    (comp (ref "R61")
      (value "10k")
      (footprint "RESC1005X40N")
      (description "RES 10k OHM 1% 1/16W 0402")
      (fields
        (field (name "PART NUMBER") "R0402_10K_1%_0.0625W")
        (field (name "POWER") "0.0625W")
        (field (name "AUTHOR") "Michal Beldyga")
      )
      (libsource (lib "") (part "Resistor - 1%_1"))
    )
    (comp (ref "R62")
      (value "374k")
      (footprint "RESC1005X40N")
      (description "RES 374k OHM 1% 1/16W 0402")
      (fields
        (field (name "PART NUMBER") "R0402_374K_1%_0.0625W")
        (field (name "POWER") "0.0625W")
        (field (name "AUTHOR") "Michal Beldyga")
      )
      (libsource (lib "") (part "Resistor - 1%_1"))
    )
    (comp (ref "R63")
      (value "10k")
      (footprint "RESC1005X40N")
      (description "RES 10k OHM 1% 1/16W 0402")
      (fields
        (field (name "PART NUMBER") "R0402_10K_1%_0.0625W")
        (field (name "POWER") "0.0625W")
        (field (name "AUTHOR") "Michal Beldyga")
      )
      (libsource (lib "") (part "Resistor - 1%_1"))
    )
    (comp (ref "R64")
      (value "1M91")
      (footprint "RESC1005X40N")
      (description "RES 1M91 OHM 1% 1/16W 0402")
      (fields
        (field (name "PART NUMBER") "R0402_1M91_1%_0.0625W")
        (field (name "POWER") "0.0625W")
        (field (name "AUTHOR") "Michal Beldyga")
      )
      (libsource (lib "") (part "Resistor - 1%_1"))
    )
    (comp (ref "R65")
      (value "12k")
      (footprint "RESC1005X40N")
      (description "Resistor - 1%")
      (fields
        (field (name "TOLERANCE") "±1%")
        (field (name "PART NUMBER") "R0402_12K_1%_0.0625W_100PPM")
        (field (name "POWER") "0.0625W")
        (field (name "AUTHOR") "CERN DEM JLC")
      )
      (libsource (lib "Resistors") (part "Resistor - 1%"))
    )
    (comp (ref "R66")
      (value "0")
      (footprint "RESC1005X40N")
      (description "Resistor")
      (fields
        (field (name "PART NUMBER") "R0402_0R_JUMPER")
        (field (name "MANUFACTURER") "GENERIC")
        (field (name "AUTHOR") "CERN DEM JLC")
      )
      (libsource (lib "Resistors") (part "Resistor"))
    )
    (comp (ref "R67")
      (value "12k")
      (footprint "RESC1005X40N")
      (description "Resistor - 1%")
      (fields
        (field (name "TOLERANCE") "±1%")
        (field (name "PART NUMBER") "R0402_12K_1%_0.0625W_100PPM")
        (field (name "POWER") "0.0625W")
        (field (name "AUTHOR") "CERN DEM JLC")
      )
      (libsource (lib "Resistors") (part "Resistor - 1%"))
    )
    (comp (ref "R68")
      (value "7k32")
      (footprint "RESC1608X55N")
      (description "Resistor - 0.1%")
      (fields
        (field (name "TOLERANCE") "±0.1%")
        (field (name "PART NUMBER") "R0603_7K32_0.1%_0.063W_10PPM")
        (field (name "POWER") "0.063W")
        (field (name "AUTHOR") "CERN DEM JLC")
      )
      (libsource (lib "Resistors") (part "Resistor - 0.1%"))
    )
    (comp (ref "R69")
      (value "100k")
      (footprint "RESC1005X40N")
      (description "Resistor - 1%")
      (fields
        (field (name "TOLERANCE") "±1%")
        (field (name "PART NUMBER") "R0402_100K_1%_0.0625W_100PPM")
        (field (name "POWER") "0.0625W")
        (field (name "AUTHOR") "CERN DEM JLC")
      )
      (libsource (lib "Resistors") (part "Resistor - 1%"))
    )
    (comp (ref "R70")
      (value "1k")
      (footprint "RESC1005X40N")
      (description "Resistor - 1%")
      (fields
        (field (name "TOLERANCE") "±1%")
        (field (name "PART NUMBER") "R0402_1K_1%_0.0625W_100PPM")
        (field (name "POWER") "0.0625W")
        (field (name "AUTHOR") "CERN DEM JLC")
      )
      (libsource (lib "Resistors") (part "Resistor - 1%"))
    )
    (comp (ref "R71")
      (value "100k")
      (footprint "RESC1005X40N")
      (description "Resistor - 1%")
      (fields
        (field (name "TOLERANCE") "±1%")
        (field (name "PART NUMBER") "R0402_100K_1%_0.0625W_100PPM")
        (field (name "POWER") "0.0625W")
        (field (name "AUTHOR") "CERN DEM JLC")
      )
      (libsource (lib "Resistors") (part "Resistor - 1%"))
    )
    (comp (ref "R72")
      (value "1M91")
      (footprint "RESC1005X40N")
      (description "RES 1M91 OHM 1% 1/16W 0402")
      (fields
        (field (name "PART NUMBER") "R0402_1M91_1%_0.0625W")
        (field (name "POWER") "0.0625W")
        (field (name "AUTHOR") "Michal Beldyga")
      )
      (libsource (lib "") (part "Resistor - 1%_1"))
    )
    (comp (ref "R73")
      (value "100k")
      (footprint "RESC1005X40N")
      (description "Resistor - 1%")
      (fields
        (field (name "TOLERANCE") "±1%")
        (field (name "PART NUMBER") "R0402_100K_1%_0.0625W_100PPM")
        (field (name "POWER") "0.0625W")
        (field (name "AUTHOR") "CERN DEM JLC")
      )
      (libsource (lib "Resistors") (part "Resistor - 1%"))
    )
    (comp (ref "R74")
      (value "100k")
      (footprint "RESC1005X40N")
      (description "Resistor - 1%")
      (fields
        (field (name "TOLERANCE") "±1%")
        (field (name "PART NUMBER") "R0402_100K_1%_0.0625W_100PPM")
        (field (name "POWER") "0.0625W")
        (field (name "AUTHOR") "CERN DEM JLC")
      )
      (libsource (lib "Resistors") (part "Resistor - 1%"))
    )
    (comp (ref "R75")
      (value "12k")
      (footprint "RESC1005X40N")
      (description "Resistor - 1%")
      (fields
        (field (name "TOLERANCE") "±1%")
        (field (name "PART NUMBER") "R0402_12K_1%_0.0625W_100PPM")
        (field (name "POWER") "0.0625W")
        (field (name "AUTHOR") "CERN DEM JLC")
      )
      (libsource (lib "Resistors") (part "Resistor - 1%"))
    )
    (comp (ref "R76")
      (value "1k")
      (footprint "RESC1005X40N")
      (description "Resistor - 1%")
      (fields
        (field (name "TOLERANCE") "±1%")
        (field (name "PART NUMBER") "R0402_1K_1%_0.0625W_100PPM")
        (field (name "POWER") "0.0625W")
        (field (name "AUTHOR") "CERN DEM JLC")
      )
      (libsource (lib "Resistors") (part "Resistor - 1%"))
    )
    (comp (ref "R85")
      (value "10k")
      (footprint "RESC1005X35N")
      (description "Resistor - 0.1%")
      (fields
        (field (name "TOLERANCE") "±0.1%")
        (field (name "PART NUMBER") "R0402_10K_0.1%_0.063W_25PPM")
        (field (name "POWER") "0.063W")
        (field (name "AUTHOR") "CERN DEM JMW")
      )
      (libsource (lib "Resistors") (part "Resistor - 0.1%"))
    )
    (comp (ref "R86")
      (value "10k")
      (footprint "RESC1005X35N")
      (description "Resistor - 0.1%")
      (fields
        (field (name "TOLERANCE") "±0.1%")
        (field (name "PART NUMBER") "R0402_10K_0.1%_0.063W_25PPM")
        (field (name "POWER") "0.063W")
        (field (name "AUTHOR") "CERN DEM JMW")
      )
      (libsource (lib "Resistors") (part "Resistor - 0.1%"))
    )
    (comp (ref "R87")
      (value "10k")
      (footprint "RESC1005X35N")
      (description "Resistor - 0.1%")
      (fields
        (field (name "TOLERANCE") "±0.1%")
        (field (name "PART NUMBER") "R0402_10K_0.1%_0.063W_25PPM")
        (field (name "POWER") "0.063W")
        (field (name "AUTHOR") "CERN DEM JMW")
      )
      (libsource (lib "Resistors") (part "Resistor - 0.1%"))
    )
    (comp (ref "R88")
      (value "10k")
      (footprint "RESC1005X40N")
      (description "RES 10k OHM 1% 1/16W 0402")
      (fields
        (field (name "PART NUMBER") "R0402_10K_1%_0.0625W")
        (field (name "POWER") "0.0625W")
        (field (name "AUTHOR") "Michal Beldyga")
      )
      (libsource (lib "") (part "Resistor - 1%_1"))
    )
    (comp (ref "R89")
      (value "10k")
      (footprint "RESC1005X35N")
      (description "Resistor - 0.1%")
      (fields
        (field (name "TOLERANCE") "±0.1%")
        (field (name "PART NUMBER") "R0402_10K_0.1%_0.063W_25PPM")
        (field (name "POWER") "0.063W")
        (field (name "AUTHOR") "CERN DEM JMW")
      )
      (libsource (lib "Resistors") (part "Resistor - 0.1%"))
    )
    (comp (ref "R93")
      (value "75")
      (footprint "RESC1005X40N")
      (description "Resistor - 1%")
      (fields
        (field (name "PART NUMBER") "R0402_75R_1%_0.0625W_100PPM")
        (field (name "POWER") "0.0625W")
        (field (name "AUTHOR") "CERN DEM JLC")
      )
      (libsource (lib "Resistors") (part "Resistor - 1%"))
    )
    (comp (ref "T8")
      (value "BSC050N03LSGATMA1")
      (footprint "INFINEON_PG-TDSON-8")
      (description "30V 80A N-Channel OptiMOS 3 Power-MOSFET")
      (fields (field (name "MANUFACTURER") "INFINEON") (field (name "AUTHOR") "CERN DEM JLC"))
      (libsource (lib "ICs And Semiconductors") (part "BSC050N03"))
    )
    (comp (ref "T9")
      (value "BSC050N03LSGATMA1")
      (footprint "INFINEON_PG-TDSON-8")
      (description "30V 80A N-Channel OptiMOS 3 Power-MOSFET")
      (fields (field (name "MANUFACTURER") "INFINEON") (field (name "AUTHOR") "CERN DEM JLC"))
      (libsource (lib "ICs And Semiconductors") (part "BSC050N03"))
    )
  )
  (nets
    (net (code "1") (name "/ADP_COMP1") (class "Default")
      (node (ref "C78") (pin "2") (pinfunction "2_2") (pintype "passive"))
      (node (ref "IC17") (pin "8") (pinfunction "COMP1_8") (pintype "input"))
      (node (ref "R67") (pin "2") (pinfunction "2_2") (pintype "passive"))
    )
    (net (code "2") (name "/ADP_COMP2") (class "Default")
      (node (ref "C79") (pin "2") (pinfunction "2_2") (pintype "passive"))
      (node (ref "IC17") (pin "12") (pinfunction "COMP2_12") (pintype "input"))
      (node (ref "R68") (pin "2") (pinfunction "2_2") (pintype "passive"))
    )
    (net (code "3") (name "/ADP_VREG") (class "Default")
      (node (ref "C84") (pin "2") (pinfunction "2_2") (pintype "passive"))
      (node (ref "IC17") (pin "16") (pinfunction "VREG_16") (pintype "output"))
      (node (ref "IC17") (pin "4") (pinfunction "SYNC/FREQ_4") (pintype "input"))
      (node (ref "IC17") (pin "5") (pinfunction "SEQ_5") (pintype "input"))
    )
    (net (code "4") (name "/BG") (class "Default")
      (node (ref "IC13") (pin "13") (pinfunction "BG_13") (pintype "output"))
      (node (ref "T9") (pin "4") (pinfunction "G_4") (pintype "passive"))
    )
    (net (code "5") (name "/BOOST") (class "Default")
      (node (ref "C32") (pin "2") (pinfunction "2_2") (pintype "passive"))
      (node (ref "D2") (pin "1") (pinfunction "C_1") (pintype "passive"))
      (node (ref "IC13") (pin "14") (pinfunction "BOOST_14") (pintype "power_in"))
    )
    (net (code "6") (name "/BUCK_FB") (class "Default")
      (node (ref "IC13") (pin "4") (pinfunction "VFB_4") (pintype "input"))
      (node (ref "R57") (pin "2") (pinfunction "2_2") (pintype "passive"))
    )
    (net (code "7") (name "/INTVCC") (class "Default")
      (node (ref "C43") (pin "1") (pinfunction "1_1") (pintype "passive"))
      (node (ref "D2") (pin "2") (pinfunction "A_2") (pintype "passive"))
      (node (ref "IC13") (pin "10") (pinfunction "INTVCC_10") (pintype "power_in"))
      (node (ref "IC13") (pin "8") (pinfunction "PLLIN/SPREAD_8") (pintype "input"))
      (node (ref "IC13") (pin "9") (pinfunction "MODE_9") (pintype "input"))
    )
    (net (code "8") (name "/P5V4_PG") (class "Default")
      (node (ref "IC13") (pin "6") (pinfunction "RUN_6") (pintype "input"))
      (node (ref "IC14") (pin "4") (pinfunction "PG_4") (pintype "output"))
      (node (ref "R58") (pin "2") (pinfunction "2_2") (pintype "passive"))
    )
    (net (code "9") (name "/P12V0_PG") (class "Default")
      (node (ref "IC14") (pin "3") (pinfunction "EN/UV_3") (pintype "input"))
      (node (ref "IC15") (pin "4") (pinfunction "PG_4") (pintype "passive"))
      (node (ref "R88") (pin "1") (pinfunction "1_1") (pintype "passive"))
    )
    (net (code "10") (name "/POWER_IN") (class "Default")
      (node (ref "C15") (pin "2") (pinfunction "2_2") (pintype "passive"))
      (node (ref "C18") (pin "2") (pinfunction "2_2") (pintype "passive"))
      (node (ref "C19") (pin "2") (pinfunction "2_2") (pintype "passive"))
      (node (ref "C20") (pin "2") (pinfunction "2_2") (pintype "passive"))
      (node (ref "C21") (pin "2") (pinfunction "2_2") (pintype "passive"))
      (node (ref "C22") (pin "2") (pinfunction "2_2") (pintype "passive"))
      (node (ref "C23") (pin "2") (pinfunction "2_2") (pintype "passive"))
      (node (ref "C58") (pin "2") (pinfunction "2_2") (pintype "passive"))
      (node (ref "C59") (pin "2") (pinfunction "2_2") (pintype "passive"))
      (node (ref "C60") (pin "2") (pinfunction "2_2") (pintype "passive"))
      (node (ref "C61") (pin "2") (pinfunction "2_2") (pintype "passive"))
      (node (ref "C62") (pin "1") (pinfunction "1_1") (pintype "passive"))
      (node (ref "IC13") (pin "12") (pinfunction "VIN_12") (pintype "power_in"))
      (node (ref "IC15") (pin "8") (pinfunction "VIN_8") (pintype "passive"))
      (node (ref "L1") (pin "1") (pinfunction "1_1") (pintype "passive"))
      (node (ref "T8") (pin "D") (pinfunction "D_D") (pintype "passive"))
    )
    (net (code "11") (name "/SUPPLY_EN") (class "Default")
      (node (ref "IC15") (pin "1") (pinfunction "EN_1") (pintype "passive"))
    )
    (net (code "12") (name "/SW") (class "Default")
      (node (ref "C32") (pin "1") (pinfunction "1_1") (pintype "passive"))
      (node (ref "IC13") (pin "16") (pinfunction "SW_16") (pintype "passive"))
      (node (ref "L5") (pin "1") (pinfunction "1_1") (pintype "passive"))
      (node (ref "T8") (pin "1") (pinfunction "S_1") (pintype "passive"))
      (node (ref "T8") (pin "2") (pinfunction "S_2") (pintype "passive"))
      (node (ref "T8") (pin "3") (pinfunction "S_3") (pintype "passive"))
      (node (ref "T9") (pin "D") (pinfunction "D_D") (pintype "passive"))
    )
    (net (code "13") (name "/TG") (class "Default")
      (node (ref "IC13") (pin "15") (pinfunction "TG_15") (pintype "output"))
      (node (ref "T8") (pin "4") (pinfunction "G_4") (pintype "passive"))
    )
    (net (code "14") (name "GND") (class "Default")
      (node (ref "C102") (pin "1") (pinfunction "1_1") (pintype "passive"))
      (node (ref "C15") (pin "1") (pinfunction "1_1") (pintype "passive"))
      (node (ref "C16") (pin "2") (pinfunction "2_2") (pintype "passive"))
      (node (ref "C17") (pin "1") (pinfunction "1_1") (pintype "passive"))
      (node (ref "C18") (pin "1") (pinfunction "1_1") (pintype "passive"))
      (node (ref "C19") (pin "1") (pinfunction "1_1") (pintype "passive"))
      (node (ref "C20") (pin "1") (pinfunction "1_1") (pintype "passive"))
      (node (ref "C21") (pin "1") (pinfunction "1_1") (pintype "passive"))
      (node (ref "C22") (pin "1") (pinfunction "1_1") (pintype "passive"))
      (node (ref "C23") (pin "1") (pinfunction "1_1") (pintype "passive"))
      (node (ref "C24") (pin "1") (pinfunction "1_1") (pintype "passive"))
      (node (ref "C25") (pin "1") (pinfunction "1_1") (pintype "passive"))
      (node (ref "C26") (pin "1") (pinfunction "1_1") (pintype "passive"))
      (node (ref "C27") (pin "2") (pinfunction "2_2") (pintype "passive"))
      (node (ref "C28") (pin "1") (pinfunction "1_1") (pintype "passive"))
      (node (ref "C29") (pin "1") (pinfunction "1_1") (pintype "passive"))
      (node (ref "C30") (pin "1") (pinfunction "1_1") (pintype "passive"))
      (node (ref "C31") (pin "1") (pinfunction "1_1") (pintype "passive"))
      (node (ref "C33") (pin "1") (pinfunction "1_1") (pintype "passive"))
      (node (ref "C34") (pin "2") (pinfunction "2_2") (pintype "passive"))
      (node (ref "C35") (pin "2") (pinfunction "2_2") (pintype "passive"))
      (node (ref "C36") (pin "1") (pinfunction "1_1") (pintype "passive"))
      (node (ref "C37") (pin "1") (pinfunction "1_1") (pintype "passive"))
      (node (ref "C38") (pin "1") (pinfunction "1_1") (pintype "passive"))
      (node (ref "C39") (pin "1") (pinfunction "1_1") (pintype "passive"))
      (node (ref "C41") (pin "2") (pinfunction "2_2") (pintype "passive"))
      (node (ref "C42") (pin "1") (pinfunction "1_1") (pintype "passive"))
      (node (ref "C43") (pin "2") (pinfunction "2_2") (pintype "passive"))
      (node (ref "C44") (pin "1") (pinfunction "1_1") (pintype "passive"))
      (node (ref "C45") (pin "1") (pinfunction "1_1") (pintype "passive"))
      (node (ref "C46") (pin "1") (pinfunction "1_1") (pintype "passive"))
      (node (ref "C47") (pin "1") (pinfunction "1_1") (pintype "passive"))
      (node (ref "C51") (pin "1") (pinfunction "1_1") (pintype "passive"))
      (node (ref "C52") (pin "1") (pinfunction "1_1") (pintype "passive"))
      (node (ref "C53") (pin "1") (pinfunction "1_1") (pintype "passive"))
      (node (ref "C54") (pin "1") (pinfunction "1_1") (pintype "passive"))
      (node (ref "C55") (pin "1") (pinfunction "1_1") (pintype "passive"))
      (node (ref "C58") (pin "1") (pinfunction "1_1") (pintype "passive"))
      (node (ref "C59") (pin "1") (pinfunction "1_1") (pintype "passive"))
      (node (ref "C60") (pin "1") (pinfunction "1_1") (pintype "passive"))
      (node (ref "C61") (pin "1") (pinfunction "1_1") (pintype "passive"))
      (node (ref "C62") (pin "2") (pinfunction "2_2") (pintype "passive"))
      (node (ref "C63") (pin "1") (pinfunction "1_1") (pintype "passive"))
      (node (ref "C64") (pin "1") (pinfunction "1_1") (pintype "passive"))
      (node (ref "C65") (pin "1") (pinfunction "1_1") (pintype "passive"))
      (node (ref "C66") (pin "1") (pinfunction "1_1") (pintype "passive"))
      (node (ref "C68") (pin "1") (pinfunction "1_1") (pintype "passive"))
      (node (ref "C69") (pin "2") (pinfunction "2_2") (pintype "passive"))
      (node (ref "C70") (pin "2") (pinfunction "2_2") (pintype "passive"))
      (node (ref "C71") (pin "1") (pinfunction "1_1") (pintype "passive"))
      (node (ref "C72") (pin "1") (pinfunction "1_1") (pintype "passive"))
      (node (ref "C73") (pin "1") (pinfunction "1_1") (pintype "passive"))
      (node (ref "C74") (pin "1") (pinfunction "1_1") (pintype "passive"))
      (node (ref "C75") (pin "1") (pinfunction "1_1") (pintype "passive"))
      (node (ref "C76") (pin "1") (pinfunction "1_1") (pintype "passive"))
      (node (ref "C77") (pin "1") (pinfunction "1_1") (pintype "passive"))
      (node (ref "C78") (pin "1") (pinfunction "1_1") (pintype "passive"))
      (node (ref "C79") (pin "1") (pinfunction "1_1") (pintype "passive"))
      (node (ref "C80") (pin "1") (pinfunction "1_1") (pintype "passive"))
      (node (ref "C81") (pin "1") (pinfunction "1_1") (pintype "passive"))
      (node (ref "C82") (pin "1") (pinfunction "1_1") (pintype "passive"))
      (node (ref "C83") (pin "1") (pinfunction "1_1") (pintype "passive"))
      (node (ref "C84") (pin "1") (pinfunction "1_1") (pintype "passive"))
      (node (ref "C85") (pin "1") (pinfunction "1_1") (pintype "passive"))
      (node (ref "C86") (pin "1") (pinfunction "1_1") (pintype "passive"))
      (node (ref "C87") (pin "1") (pinfunction "1_1") (pintype "passive"))
      (node (ref "C88") (pin "1") (pinfunction "1_1") (pintype "passive"))
      (node (ref "C89") (pin "1") (pinfunction "1_1") (pintype "passive"))
      (node (ref "C90") (pin "1") (pinfunction "1_1") (pintype "passive"))
      (node (ref "C91") (pin "1") (pinfunction "1_1") (pintype "passive"))
      (node (ref "C92") (pin "1") (pinfunction "1_1") (pintype "passive"))
      (node (ref "C93") (pin "1") (pinfunction "1_1") (pintype "passive"))
      (node (ref "IC12") (pin "1") (pinfunction "GND_1") (pintype "power_in"))
      (node (ref "IC13") (pin "17") (pinfunction "PAD_17") (pintype "passive"))
      (node (ref "IC14") (pin "11") (pinfunction "GND_11") (pintype "power_in"))
      (node (ref "IC14") (pin "5") (pinfunction "ILIM_5") (pintype "input"))
      (node (ref "IC14") (pin "8") (pinfunction "GND_8") (pintype "power_in"))
      (node (ref "IC15") (pin "3") (pinfunction "AGND_3") (pintype "passive"))
      (node (ref "IC15") (pin "9") (pinfunction "PGND_9") (pintype "passive"))
      (node (ref "IC16") (pin "3") (pinfunction "GND_3") (pintype "power_in"))
      (node (ref "IC16") (pin "4") (pinfunction "GND_4") (pintype "power_in"))
      (node (ref "IC16") (pin "5") (pinfunction "GND_5") (pintype "power_in"))
      (node (ref "IC16") (pin "8") (pinfunction "GND_8") (pintype "power_in"))
      (node (ref "IC17") (pin "1") (pinfunction "PGND_1") (pintype "power_in"))
      (node (ref "IC17") (pin "15") (pinfunction "AGND_15") (pintype "power_in"))
      (node (ref "IC17") (pin "21") (pinfunction "PAD_21") (pintype "power_in"))
      (node (ref "IC17") (pin "6") (pinfunction "SLEW_6") (pintype "input"))
      (node (ref "IC18") (pin "13") (pinfunction "EP_13") (pintype "power_in"))
      (node (ref "IC18") (pin "7") (pinfunction "GND_7") (pintype "power_in"))
      (node (ref "IC20") (pin "1") (pinfunction "GND_1") (pintype "power_in"))
      (node (ref "IC23") (pin "4") (pinfunction "V-_4") (pintype "power_in"))
      (node (ref "L10") (pin "2") (pinfunction "2_2") (pintype "passive"))
      (node (ref "R47") (pin "1") (pinfunction "1_1") (pintype "passive"))
      (node (ref "R48") (pin "1") (pinfunction "1_1") (pintype "passive"))
      (node (ref "R51") (pin "2") (pinfunction "2_2") (pintype "passive"))
      (node (ref "R52") (pin "1") (pinfunction "1_1") (pintype "passive"))
      (node (ref "R56") (pin "1") (pinfunction "1_1") (pintype "passive"))
      (node (ref "R57") (pin "1") (pinfunction "1_1") (pintype "passive"))
      (node (ref "R62") (pin "1") (pinfunction "1_1") (pintype "passive"))
      (node (ref "R63") (pin "1") (pinfunction "1_1") (pintype "passive"))
      (node (ref "R69") (pin "1") (pinfunction "1_1") (pintype "passive"))
      (node (ref "R76") (pin "1") (pinfunction "1_1") (pintype "passive"))
      (node (ref "R89") (pin "1") (pinfunction "1_1") (pintype "passive"))
      (node (ref "R93") (pin "1") (pinfunction "1_1") (pintype "passive"))
      (node (ref "T9") (pin "1") (pinfunction "S_1") (pintype "passive"))
      (node (ref "T9") (pin "2") (pinfunction "S_2") (pintype "passive"))
      (node (ref "T9") (pin "3") (pinfunction "S_3") (pintype "passive"))
    )
    (net (code "15") (name "N15V0") (class "Default")
      (node (ref "C85") (pin "2") (pinfunction "2_2") (pintype "passive"))
      (node (ref "IC20") (pin "5") (pinfunction "OUT_5") (pintype "power_in"))
      (node (ref "R75") (pin "2") (pinfunction "2_2") (pintype "passive"))
    )
    (net (code "16") (name "N16V0") (class "Default")
      (node (ref "C88") (pin "2") (pinfunction "2_2") (pintype "passive"))
      (node (ref "C89") (pin "2") (pinfunction "2_2") (pintype "passive"))
      (node (ref "C90") (pin "2") (pinfunction "2_2") (pintype "passive"))
      (node (ref "IC20") (pin "2") (pinfunction "IN_2") (pintype "input"))
      (node (ref "IC20") (pin "3") (pinfunction "~{SHDN}_3") (pintype "input"))
      (node (ref "L9") (pin "2") (pinfunction "2_2") (pintype "passive"))
    )
    (net (code "17") (name "Net-(C27-Pad1)") (class "Default")
      (node (ref "C27") (pin "1") (pinfunction "1_1") (pintype "passive"))
      (node (ref "C28") (pin "2") (pinfunction "2_2") (pintype "passive"))
      (node (ref "L3") (pin "2") (pinfunction "2_2") (pintype "passive"))
      (node (ref "L4") (pin "1") (pinfunction "1_1") (pintype "passive"))
    )
    (net (code "18") (name "Net-(C50-Pad1)") (class "Default")
      (node (ref "C50") (pin "1") (pinfunction "1_1") (pintype "passive"))
      (node (ref "R56") (pin "2") (pinfunction "2_2") (pintype "passive"))
    )
    (net (code "19") (name "Net-(C80-Pad2)") (class "Default")
      (node (ref "C80") (pin "2") (pinfunction "2_2") (pintype "passive"))
      (node (ref "R67") (pin "1") (pinfunction "1_1") (pintype "passive"))
    )
    (net (code "20") (name "Net-(C81-Pad2)") (class "Default")
      (node (ref "C81") (pin "2") (pinfunction "2_2") (pintype "passive"))
      (node (ref "R68") (pin "1") (pinfunction "1_1") (pintype "passive"))
    )
    (net (code "21") (name "Net-(D3-A)") (class "Default")
      (node (ref "D3") (pin "2") (pinfunction "A_2") (pintype "passive"))
      (node (ref "IC17") (pin "2") (pinfunction "SW1_2") (pintype "output"))
      (node (ref "L7") (pin "2") (pinfunction "2_2") (pintype "passive"))
    )
    (net (code "22") (name "Net-(D3-C)") (class "Default")
      (node (ref "C72") (pin "2") (pinfunction "2_2") (pintype "passive"))
      (node (ref "C73") (pin "2") (pinfunction "2_2") (pintype "passive"))
      (node (ref "D3") (pin "1") (pinfunction "C_1") (pintype "passive"))
      (node (ref "L8") (pin "1") (pinfunction "1_1") (pintype "passive"))
      (node (ref "R64") (pin "2") (pinfunction "2_2") (pintype "passive"))
    )
    (net (code "23") (name "Net-(D4-A)") (class "Default")
      (node (ref "C86") (pin "2") (pinfunction "2_2") (pintype "passive"))
      (node (ref "C87") (pin "2") (pinfunction "2_2") (pintype "passive"))
      (node (ref "D4") (pin "2") (pinfunction "A_2") (pintype "passive"))
      (node (ref "L9") (pin "1") (pinfunction "1_1") (pintype "passive"))
      (node (ref "R74") (pin "1") (pinfunction "1_1") (pintype "passive"))
    )
    (net (code "24") (name "Net-(D4-C)") (class "Default")
      (node (ref "D4") (pin "1") (pinfunction "C_1") (pintype "passive"))
      (node (ref "IC17") (pin "20") (pinfunction "SW2_20") (pintype "output"))
      (node (ref "L10") (pin "1") (pinfunction "1_1") (pintype "passive"))
    )
    (net (code "25") (name "Net-(IC12-BST)") (class "Default")
      (node (ref "C14") (pin "1") (pinfunction "1_1") (pintype "passive"))
      (node (ref "IC12") (pin "6") (pinfunction "BST_6") (pintype "input"))
    )
    (net (code "26") (name "Net-(IC12-FB)") (class "Default")
      (node (ref "IC12") (pin "4") (pinfunction "FB_4") (pintype "input"))
      (node (ref "R46") (pin "1") (pinfunction "1_1") (pintype "passive"))
      (node (ref "R47") (pin "2") (pinfunction "2_2") (pintype "passive"))
    )
    (net (code "27") (name "Net-(IC12-SW)") (class "Default")
      (node (ref "C14") (pin "2") (pinfunction "2_2") (pintype "passive"))
      (node (ref "IC12") (pin "2") (pinfunction "SW_2") (pintype "output"))
      (node (ref "L2") (pin "1") (pinfunction "1_1") (pintype "passive"))
    )
    (net (code "28") (name "Net-(IC12-VIN)") (class "Default")
      (node (ref "C16") (pin "1") (pinfunction "1_1") (pintype "passive"))
      (node (ref "C17") (pin "2") (pinfunction "2_2") (pintype "passive"))
      (node (ref "IC12") (pin "3") (pinfunction "VIN_3") (pintype "input"))
      (node (ref "L1") (pin "2") (pinfunction "2_2") (pintype "passive"))
    )
    (net (code "29") (name "Net-(IC13-FREQ)") (class "Default")
      (node (ref "C33") (pin "2") (pinfunction "2_2") (pintype "passive"))
      (node (ref "IC13") (pin "7") (pinfunction "FREQ_7") (pintype "input"))
      (node (ref "R48") (pin "2") (pinfunction "2_2") (pintype "passive"))
    )
    (net (code "30") (name "Net-(IC13-ITH)") (class "Default")
      (node (ref "C50") (pin "2") (pinfunction "2_2") (pintype "passive"))
      (node (ref "C51") (pin "2") (pinfunction "2_2") (pintype "passive"))
      (node (ref "IC13") (pin "5") (pinfunction "ITH_5") (pintype "output"))
    )
    (net (code "31") (name "Net-(IC13-SENSE+)") (class "Default")
      (node (ref "C49") (pin "2") (pinfunction "2_2") (pintype "passive"))
      (node (ref "IC13") (pin "2") (pinfunction "SENSE+_2") (pintype "input"))
      (node (ref "R55") (pin "1") (pinfunction "1_1") (pintype "passive"))
    )
    (net (code "32") (name "Net-(IC13-SENSE-)") (class "Default")
      (node (ref "C49") (pin "1") (pinfunction "1_1") (pintype "passive"))
      (node (ref "IC13") (pin "3") (pinfunction "SENSE-_3") (pintype "input"))
      (node (ref "R49") (pin "V1") (pinfunction "V1_V1") (pintype "passive"))
    )
    (net (code "33") (name "Net-(IC13-TRACK{slash}SS)") (class "Default")
      (node (ref "C42") (pin "2") (pinfunction "2_2") (pintype "passive"))
      (node (ref "IC13") (pin "1") (pinfunction "TRACK/SS_1") (pintype "input"))
    )
    (net (code "34") (name "Net-(IC14-IN-Pad1)") (class "Default")
      (node (ref "IC14") (pin "1") (pinfunction "IN_1") (pintype "input"))
      (node (ref "IC14") (pin "2") (pinfunction "IN_2") (pintype "input"))
      (node (ref "L4") (pin "2") (pinfunction "2_2") (pintype "passive"))
    )
    (net (code "35") (name "Net-(IC14-PGFB)") (class "Default")
      (node (ref "IC14") (pin "6") (pinfunction "PGFB_6") (pintype "input"))
      (node (ref "R52") (pin "2") (pinfunction "2_2") (pintype "passive"))
      (node (ref "R53") (pin "1") (pinfunction "1_1") (pintype "passive"))
    )
    (net (code "36") (name "Net-(IC14-SET)") (class "Default")
      (node (ref "C41") (pin "1") (pinfunction "1_1") (pintype "passive"))
      (node (ref "IC14") (pin "7") (pinfunction "SET_7") (pintype "input"))
      (node (ref "R50") (pin "1") (pinfunction "1_1") (pintype "passive"))
    )
    (net (code "37") (name "Net-(IC15-BOOT)") (class "Default")
      (node (ref "C57") (pin "2") (pinfunction "2_2") (pintype "passive"))
      (node (ref "IC15") (pin "7") (pinfunction "BOOT_7") (pintype "passive"))
    )
    (net (code "38") (name "Net-(IC15-FB)") (class "Default")
      (node (ref "C67") (pin "1") (pinfunction "1_1") (pintype "passive"))
      (node (ref "IC15") (pin "2") (pinfunction "FB_2") (pintype "passive"))
      (node (ref "R59") (pin "1") (pinfunction "1_1") (pintype "passive"))
      (node (ref "R61") (pin "2") (pinfunction "2_2") (pintype "passive"))
    )
    (net (code "39") (name "Net-(IC15-MODE)") (class "Default")
      (node (ref "IC15") (pin "10") (pinfunction "MODE_10") (pintype "passive"))
      (node (ref "R62") (pin "2") (pinfunction "2_2") (pintype "passive"))
    )
    (net (code "40") (name "Net-(IC15-SS)") (class "Default")
      (node (ref "C69") (pin "1") (pinfunction "1_1") (pintype "passive"))
      (node (ref "IC15") (pin "5") (pinfunction "SS_5") (pintype "passive"))
    )
    (net (code "41") (name "Net-(IC15-SW)") (class "Default")
      (node (ref "C57") (pin "1") (pinfunction "1_1") (pintype "passive"))
      (node (ref "IC15") (pin "6") (pinfunction "SW_6") (pintype "passive"))
      (node (ref "L6") (pin "1") (pinfunction "1_1") (pintype "passive"))
    )
    (net (code "42") (name "Net-(IC16-VOUTS)") (class "Default")
      (node (ref "C76") (pin "2") (pinfunction "2_2") (pintype "passive"))
      (node (ref "IC16") (pin "6") (pinfunction "VOUTS_6") (pintype "power_in"))
      (node (ref "R66") (pin "1") (pinfunction "1_1") (pintype "passive"))
    )
    (net (code "43") (name "Net-(IC16-~{SHDN})") (class "Default")
      (node (ref "IC16") (pin "1") (pinfunction "~{SHDN}_1") (pintype "input"))
      (node (ref "R58") (pin "1") (pinfunction "1_1") (pintype "passive"))
      (node (ref "R60") (pin "2") (pinfunction "2_2") (pintype "passive"))
    )
    (net (code "44") (name "Net-(IC17-FB1)") (class "Default")
      (node (ref "IC17") (pin "7") (pinfunction "FB1_7") (pintype "input"))
      (node (ref "R64") (pin "1") (pinfunction "1_1") (pintype "passive"))
      (node (ref "R69") (pin "2") (pinfunction "2_2") (pintype "passive"))
    )
    (net (code "45") (name "Net-(IC17-FB2)") (class "Default")
      (node (ref "IC17") (pin "13") (pinfunction "FB2_13") (pintype "input"))
      (node (ref "R71") (pin "1") (pinfunction "1_1") (pintype "passive"))
      (node (ref "R72") (pin "1") (pinfunction "1_1") (pintype "passive"))
    )
    (net (code "46") (name "Net-(IC17-INBK)") (class "Default")
      (node (ref "IC17") (pin "3") (pinfunction "INBK_3") (pintype "output"))
      (node (ref "L7") (pin "1") (pinfunction "1_1") (pintype "passive"))
    )
    (net (code "47") (name "Net-(IC17-VREF)") (class "Default")
      (node (ref "C83") (pin "2") (pinfunction "2_2") (pintype "passive"))
      (node (ref "IC17") (pin "14") (pinfunction "VREF_14") (pintype "output"))
      (node (ref "R71") (pin "2") (pinfunction "2_2") (pintype "passive"))
    )
    (net (code "48") (name "Net-(IC18-ADJ)") (class "Default")
      (node (ref "IC18") (pin "5") (pinfunction "ADJ_5") (pintype "input"))
      (node (ref "R65") (pin "1") (pinfunction "1_1") (pintype "passive"))
      (node (ref "R70") (pin "2") (pinfunction "2_2") (pintype "passive"))
    )
    (net (code "49") (name "Net-(IC18-BYP)") (class "Default")
      (node (ref "C82") (pin "2") (pinfunction "2_2") (pintype "passive"))
      (node (ref "IC18") (pin "6") (pinfunction "BYP_6") (pintype "passive"))
    )
    (net (code "50") (name "Net-(IC20-ADJ)") (class "Default")
      (node (ref "IC20") (pin "4") (pinfunction "ADJ_4") (pintype "input"))
      (node (ref "R75") (pin "1") (pinfunction "1_1") (pintype "passive"))
      (node (ref "R76") (pin "2") (pinfunction "2_2") (pintype "passive"))
    )
    (net (code "51") (name "Net-(IC23A-IN+)") (class "Default")
      (node (ref "IC23") (pin "3") (pinfunction "IN+_3") (pintype "input"))
      (node (ref "R87") (pin "1") (pinfunction "1_1") (pintype "passive"))
      (node (ref "R89") (pin "2") (pinfunction "2_2") (pintype "passive"))
    )
    (net (code "52") (name "Net-(IC23A-IN-)") (class "Default")
      (node (ref "IC23") (pin "2") (pinfunction "IN-_2") (pintype "input"))
      (node (ref "R85") (pin "2") (pinfunction "2_2") (pintype "passive"))
      (node (ref "R86") (pin "2") (pinfunction "2_2") (pintype "passive"))
    )
    (net (code "53") (name "Net-(L5-Pad2)") (class "Default")
      (node (ref "L5") (pin "2") (pinfunction "2_2") (pintype "passive"))
      (node (ref "R49") (pin "I2") (pinfunction "I2_I2") (pintype "passive"))
    )
    (net (code "54") (name "Net-(R49-PadV2)") (class "Default")
      (node (ref "R49") (pin "V2") (pinfunction "V2_V2") (pintype "passive"))
      (node (ref "R55") (pin "2") (pinfunction "2_2") (pintype "passive"))
    )
    (net (code "55") (name "Net-(R50-Pad2)") (class "Default")
      (node (ref "R50") (pin "2") (pinfunction "2_2") (pintype "passive"))
      (node (ref "R51") (pin "1") (pinfunction "1_1") (pintype "passive"))
    )
    (net (code "56") (name "Net-(R53-Pad2)") (class "Default")
      (node (ref "R53") (pin "2") (pinfunction "2_2") (pintype "passive"))
      (node (ref "R54") (pin "1") (pinfunction "1_1") (pintype "passive"))
    )
    (net (code "57") (name "Net-(R61-Pad1)") (class "Default")
      (node (ref "R61") (pin "1") (pinfunction "1_1") (pintype "passive"))
      (node (ref "R63") (pin "2") (pinfunction "2_2") (pintype "passive"))
    )
    (net (code "58") (name "Net-(R70-Pad1)") (class "Default")
      (node (ref "R70") (pin "1") (pinfunction "1_1") (pintype "passive"))
      (node (ref "R93") (pin "2") (pinfunction "2_2") (pintype "passive"))
    )
    (net (code "59") (name "Net-(R72-Pad2)") (class "Default")
      (node (ref "R72") (pin "2") (pinfunction "2_2") (pintype "passive"))
      (node (ref "R73") (pin "2") (pinfunction "2_2") (pintype "passive"))
    )
    (net (code "60") (name "Net-(R73-Pad1)") (class "Default")
      (node (ref "R73") (pin "1") (pinfunction "1_1") (pintype "passive"))
      (node (ref "R74") (pin "2") (pinfunction "2_2") (pintype "passive"))
    )
    (net (code "61") (name "P2V5_REF") (class "Default")
      (node (ref "IC23") (pin "1") (pinfunction "OUT_1") (pintype "output"))
      (node (ref "R85") (pin "1") (pinfunction "1_1") (pintype "passive"))
      (node (ref "R86") (pin "1") (pinfunction "1_1") (pintype "passive"))
    )
    (net (code "62") (name "P3V3") (class "Default")
      (node (ref "C24") (pin "2") (pinfunction "2_2") (pintype "passive"))
      (node (ref "C25") (pin "2") (pinfunction "2_2") (pintype "passive"))
      (node (ref "C26") (pin "2") (pinfunction "2_2") (pintype "passive"))
      (node (ref "L2") (pin "2") (pinfunction "2_2") (pintype "passive"))
      (node (ref "R46") (pin "2") (pinfunction "2_2") (pintype "passive"))
      (node (ref "R88") (pin "2") (pinfunction "2_2") (pintype "passive"))
    )
    (net (code "63") (name "P5V0_REF") (class "Default")
      (node (ref "C77") (pin "2") (pinfunction "2_2") (pintype "passive"))
      (node (ref "IC16") (pin "7") (pinfunction "VOUTF_7") (pintype "power_in"))
      (node (ref "R66") (pin "2") (pinfunction "2_2") (pintype "passive"))
      (node (ref "R87") (pin "2") (pinfunction "2_2") (pintype "passive"))
    )
    (net (code "64") (name "P5V4A") (class "Default")
      (node (ref "C102") (pin "2") (pinfunction "2_2") (pintype "passive"))
      (node (ref "C29") (pin "2") (pinfunction "2_2") (pintype "passive"))
      (node (ref "C30") (pin "2") (pinfunction "2_2") (pintype "passive"))
      (node (ref "C31") (pin "2") (pinfunction "2_2") (pintype "passive"))
      (node (ref "C68") (pin "2") (pinfunction "2_2") (pintype "passive"))
      (node (ref "IC14") (pin "10") (pinfunction "OUT_10") (pintype "output"))
      (node (ref "IC14") (pin "9") (pinfunction "OUTS_9") (pintype "output"))
      (node (ref "IC16") (pin "2") (pinfunction "VIN_2") (pintype "input"))
      (node (ref "IC23") (pin "8") (pinfunction "V+_8") (pintype "power_in"))
      (node (ref "R54") (pin "2") (pinfunction "2_2") (pintype "passive"))
      (node (ref "R60") (pin "1") (pinfunction "1_1") (pintype "passive"))
    )
    (net (code "65") (name "P12V0") (class "Default")
      (node (ref "C63") (pin "2") (pinfunction "2_2") (pintype "passive"))
      (node (ref "C64") (pin "2") (pinfunction "2_2") (pintype "passive"))
      (node (ref "C65") (pin "2") (pinfunction "2_2") (pintype "passive"))
      (node (ref "C66") (pin "2") (pinfunction "2_2") (pintype "passive"))
      (node (ref "C67") (pin "2") (pinfunction "2_2") (pintype "passive"))
      (node (ref "C91") (pin "2") (pinfunction "2_2") (pintype "passive"))
      (node (ref "C92") (pin "2") (pinfunction "2_2") (pintype "passive"))
      (node (ref "C93") (pin "2") (pinfunction "2_2") (pintype "passive"))
      (node (ref "IC17") (pin "11") (pinfunction "EN2_11") (pintype "input"))
      (node (ref "IC17") (pin "17") (pinfunction "PVIN1_17") (pintype "power_in"))
      (node (ref "IC17") (pin "18") (pinfunction "PVINSYSS_18") (pintype "power_in"))
      (node (ref "IC17") (pin "19") (pinfunction "PVIN2_19") (pintype "power_in"))
      (node (ref "IC17") (pin "9") (pinfunction "EN1_9") (pintype "input"))
      (node (ref "L3") (pin "1") (pinfunction "1_1") (pintype "passive"))
      (node (ref "L6") (pin "2") (pinfunction "2_2") (pintype "passive"))
      (node (ref "R59") (pin "2") (pinfunction "2_2") (pintype "passive"))
    )
    (net (code "66") (name "P15V0") (class "Default")
      (node (ref "C75") (pin "2") (pinfunction "2_2") (pintype "passive"))
      (node (ref "IC18") (pin "2") (pinfunction "OUT_2") (pintype "power_in"))
      (node (ref "IC18") (pin "3") (pinfunction "OUT_3") (pintype "power_in"))
      (node (ref "R65") (pin "2") (pinfunction "2_2") (pintype "passive"))
    )
    (net (code "67") (name "P16V0") (class "Default")
      (node (ref "C70") (pin "1") (pinfunction "1_1") (pintype "passive"))
      (node (ref "C71") (pin "2") (pinfunction "2_2") (pintype "passive"))
      (node (ref "C74") (pin "2") (pinfunction "2_2") (pintype "passive"))
      (node (ref "IC18") (pin "10") (pinfunction "IN_10") (pintype "input"))
      (node (ref "IC18") (pin "11") (pinfunction "IN_11") (pintype "input"))
      (node (ref "IC18") (pin "8") (pinfunction "~{SHDN}_8") (pintype "input"))
      (node (ref "L8") (pin "2") (pinfunction "2_2") (pintype "passive"))
    )
    (net (code "68") (name "VBUCK") (class "Default")
      (node (ref "C34") (pin "1") (pinfunction "1_1") (pintype "passive"))
      (node (ref "C35") (pin "1") (pinfunction "1_1") (pintype "passive"))
      (node (ref "C36") (pin "2") (pinfunction "2_2") (pintype "passive"))
      (node (ref "C37") (pin "2") (pinfunction "2_2") (pintype "passive"))
      (node (ref "C38") (pin "2") (pinfunction "2_2") (pintype "passive"))
      (node (ref "C39") (pin "2") (pinfunction "2_2") (pintype "passive"))
      (node (ref "C44") (pin "2") (pinfunction "2_2") (pintype "passive"))
      (node (ref "C45") (pin "2") (pinfunction "2_2") (pintype "passive"))
      (node (ref "C46") (pin "2") (pinfunction "2_2") (pintype "passive"))
      (node (ref "C47") (pin "2") (pinfunction "2_2") (pintype "passive"))
      (node (ref "C52") (pin "2") (pinfunction "2_2") (pintype "passive"))
      (node (ref "C53") (pin "2") (pinfunction "2_2") (pintype "passive"))
      (node (ref "C54") (pin "2") (pinfunction "2_2") (pintype "passive"))
      (node (ref "C55") (pin "2") (pinfunction "2_2") (pintype "passive"))
      (node (ref "IC13") (pin "11") (pinfunction "EXTVCC_11") (pintype "power_in"))
      (node (ref "R49") (pin "I1") (pinfunction "I1_I1") (pintype "passive"))
    )
    (net (code "69") (name "unconnected-(IC12-EN-Pad5)") (class "Default")
      (node (ref "IC12") (pin "5") (pinfunction "EN_5") (pintype "input+no_connect"))
    )
    (net (code "70") (name "unconnected-(IC17-SS-Pad10)") (class "Default")
      (node (ref "IC17") (pin "10") (pinfunction "SS_10") (pintype "input+no_connect"))
    )
    (net (code "71") (name "unconnected-(IC18-NC-Pad1)") (class "Default")
      (node (ref "IC18") (pin "1") (pinfunction "NC_1") (pintype "passive"))
    )
    (net (code "72") (name "unconnected-(IC18-NC-Pad4)") (class "Default")
      (node (ref "IC18") (pin "4") (pinfunction "NC_4") (pintype "passive"))
    )
    (net (code "73") (name "unconnected-(IC18-NC-Pad9)") (class "Default")
      (node (ref "IC18") (pin "9") (pinfunction "NC_9") (pintype "passive"))
    )
    (net (code "74") (name "unconnected-(IC18-NC-Pad12)") (class "Default")
      (node (ref "IC18") (pin "12") (pinfunction "NC_12") (pintype "passive"))
    )
  )
)
